# mk312lite_V4a.net
KiCad netlist of a schematic drawn in EAGLE
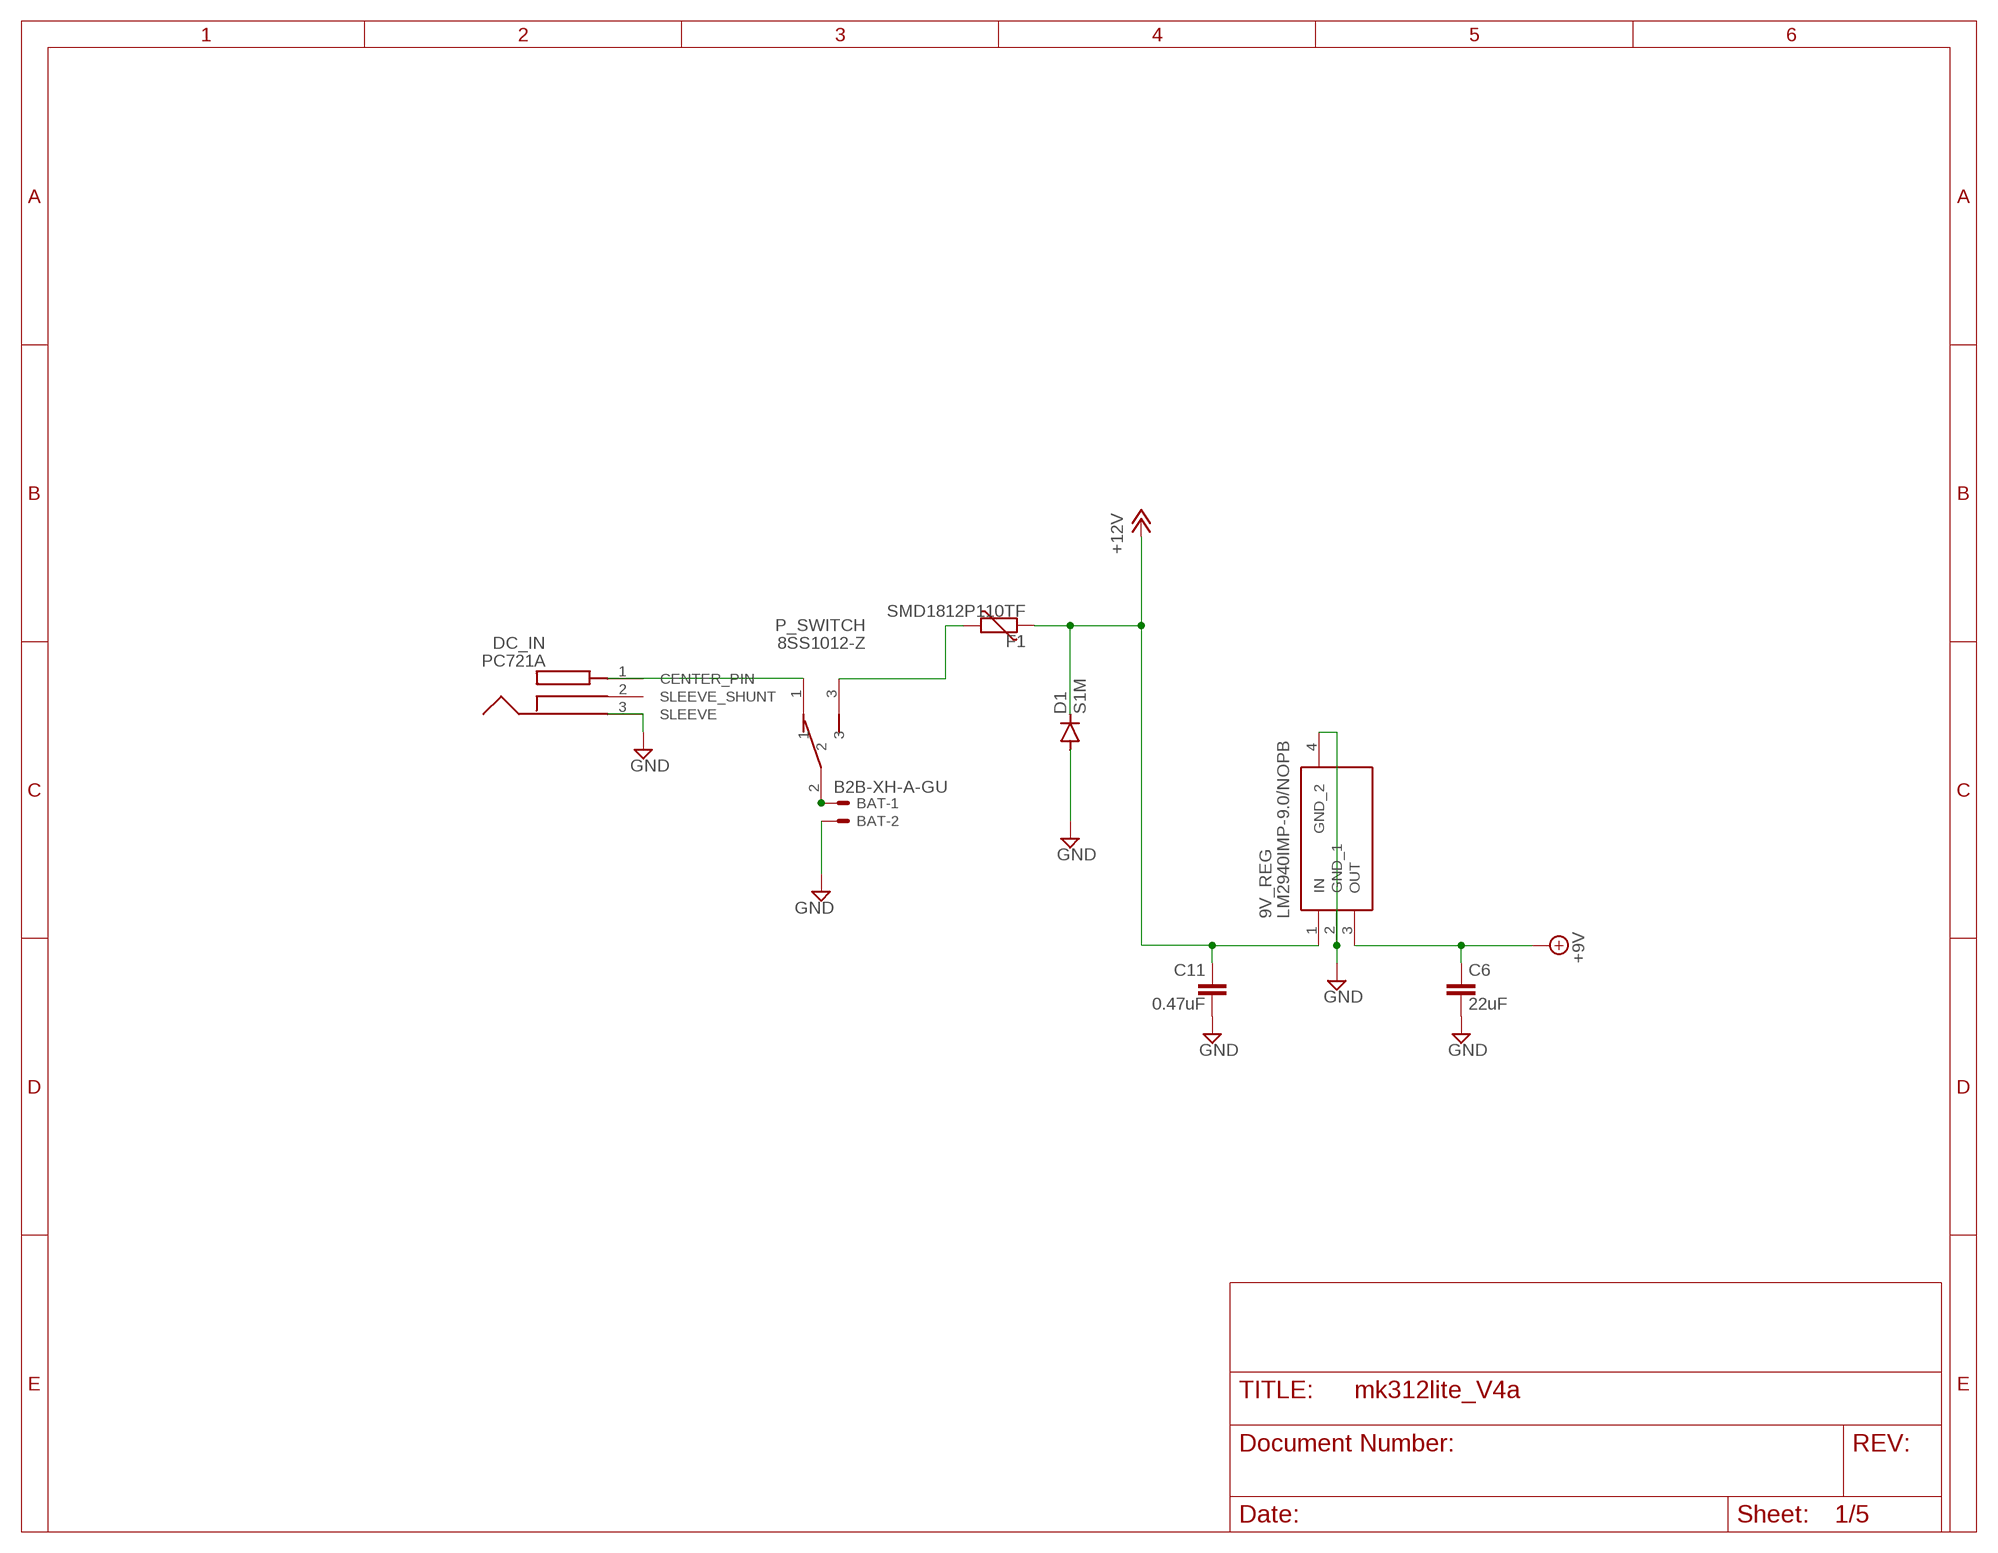
[diagram p0: schematic, sheet 1]
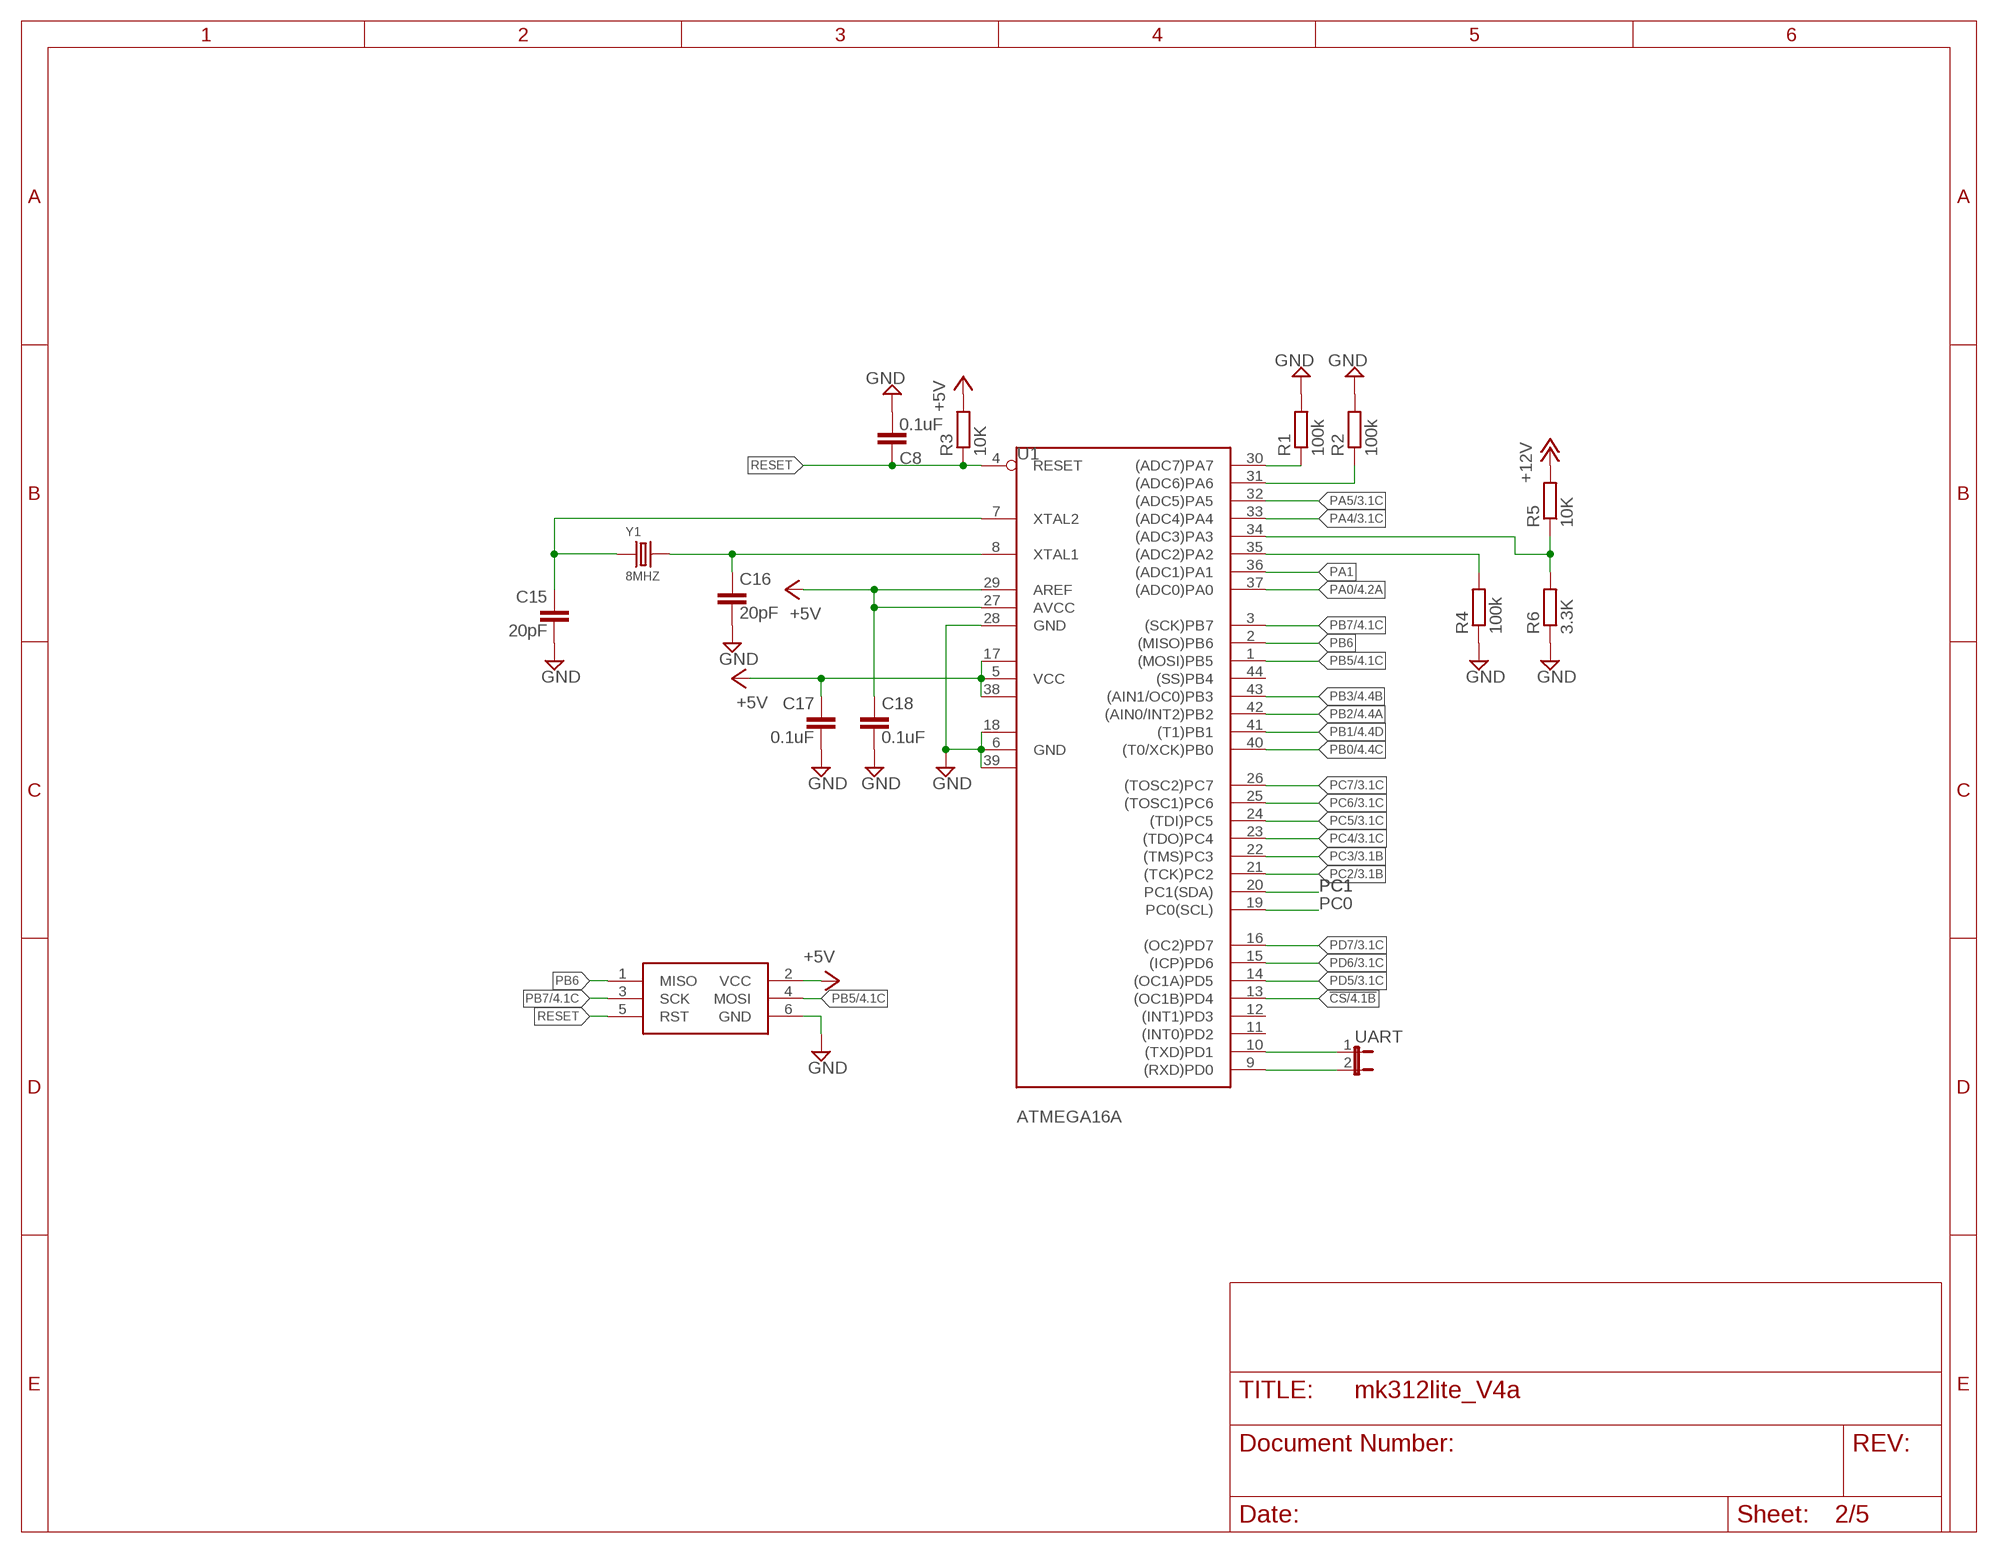
[diagram p1: schematic, sheet 2]
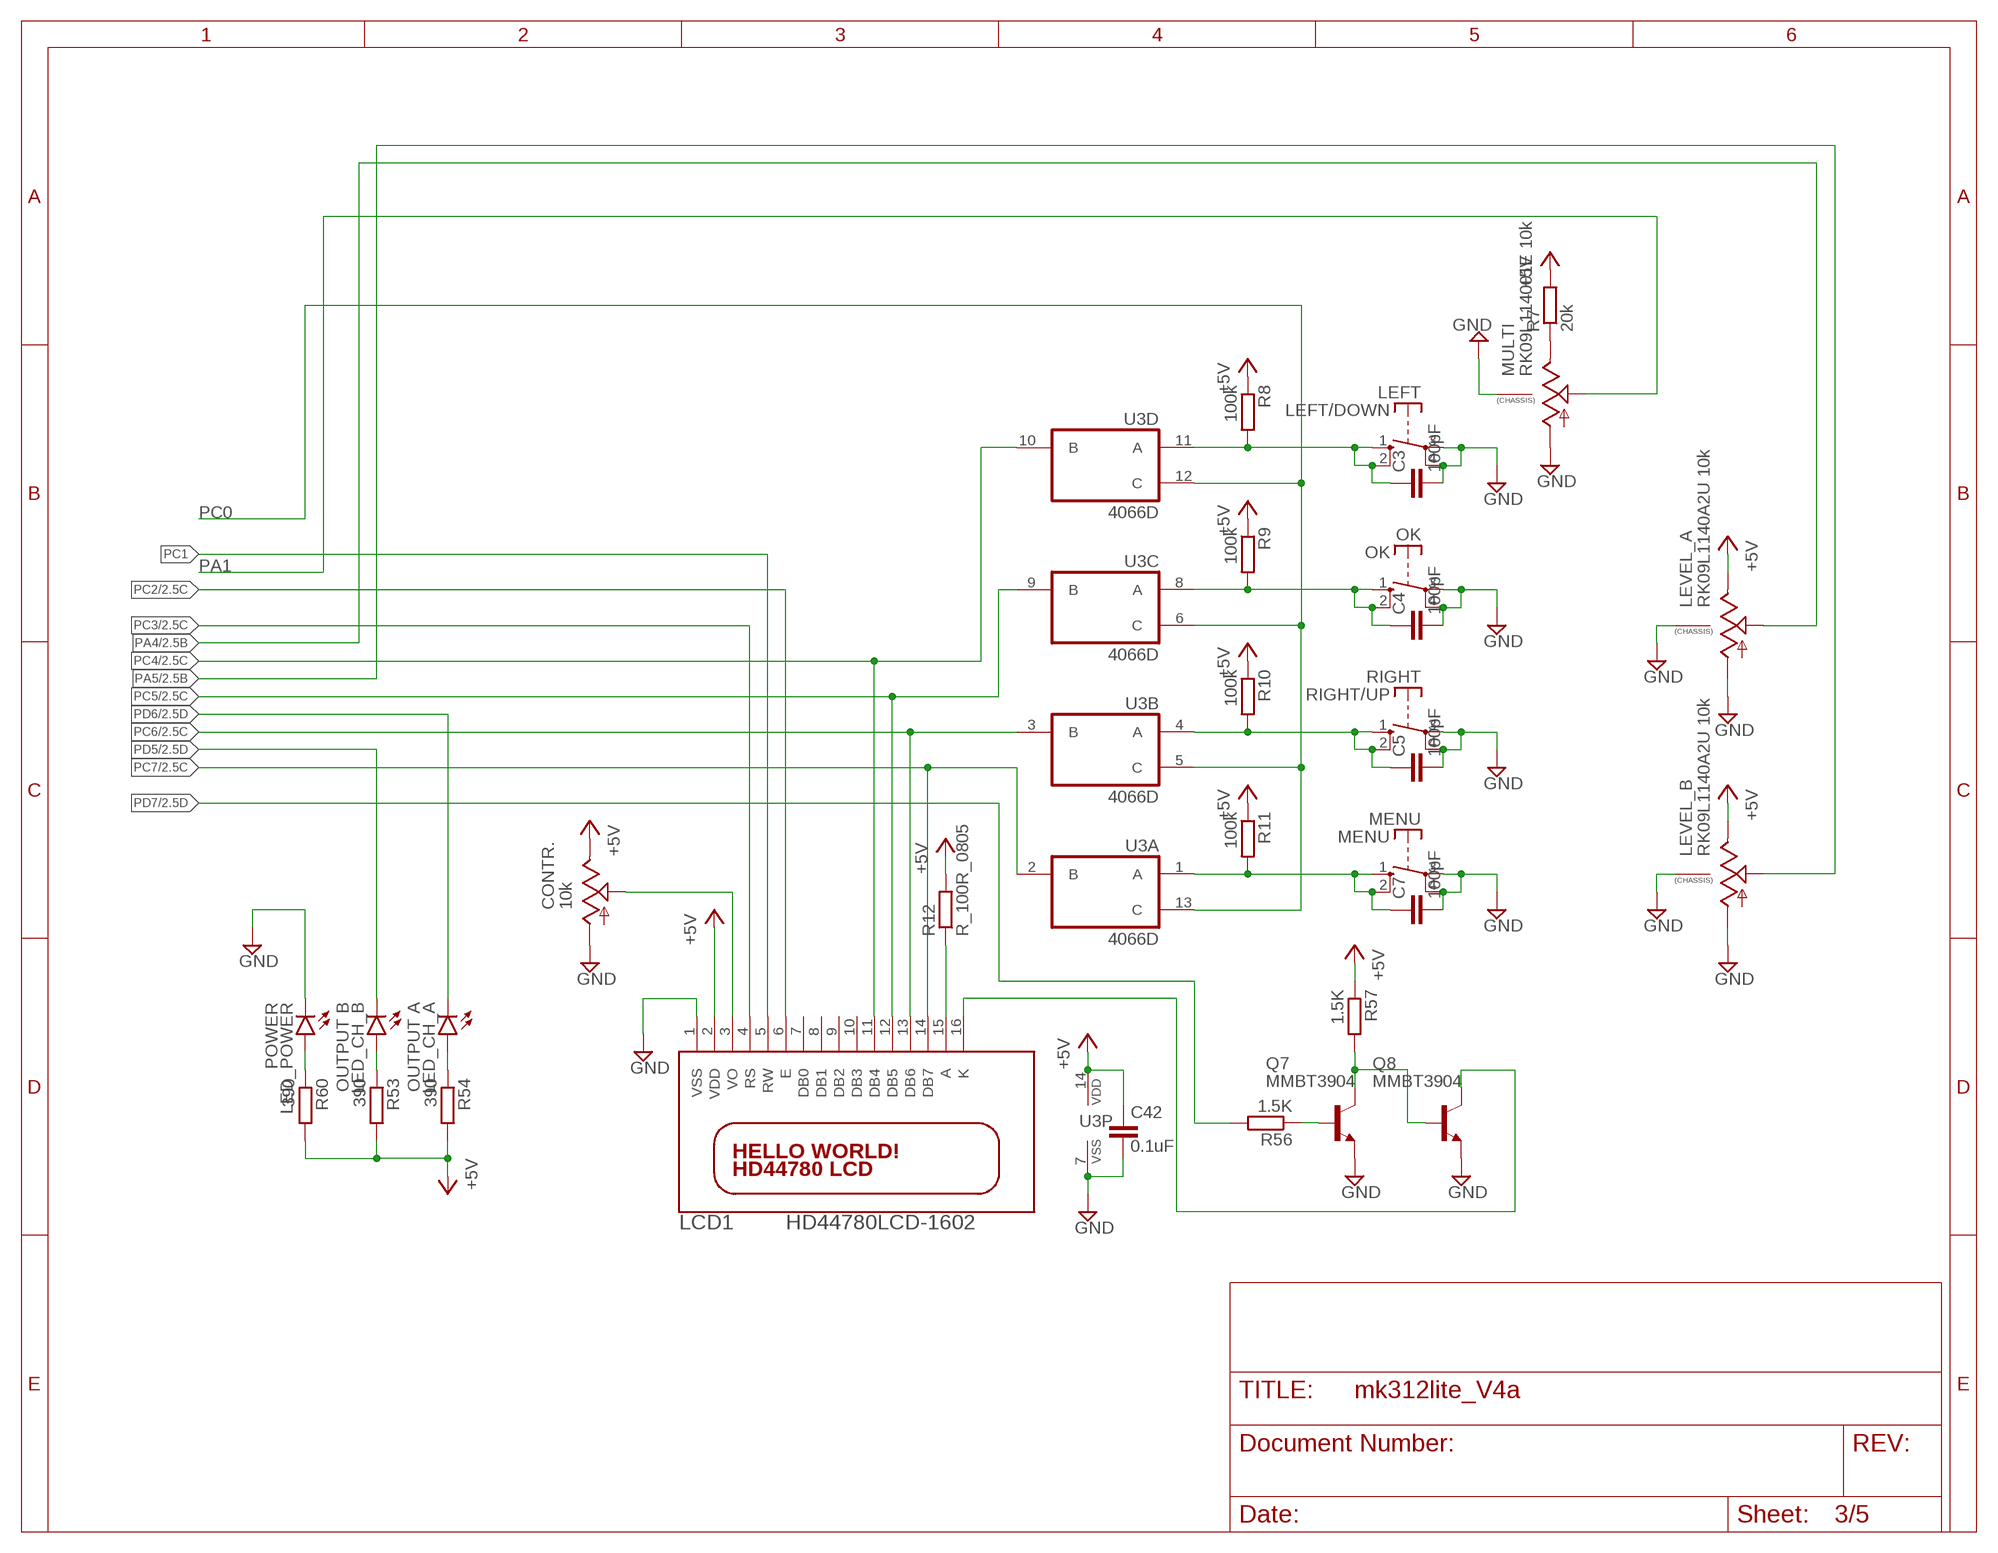
[diagram p2: schematic, sheet 3]
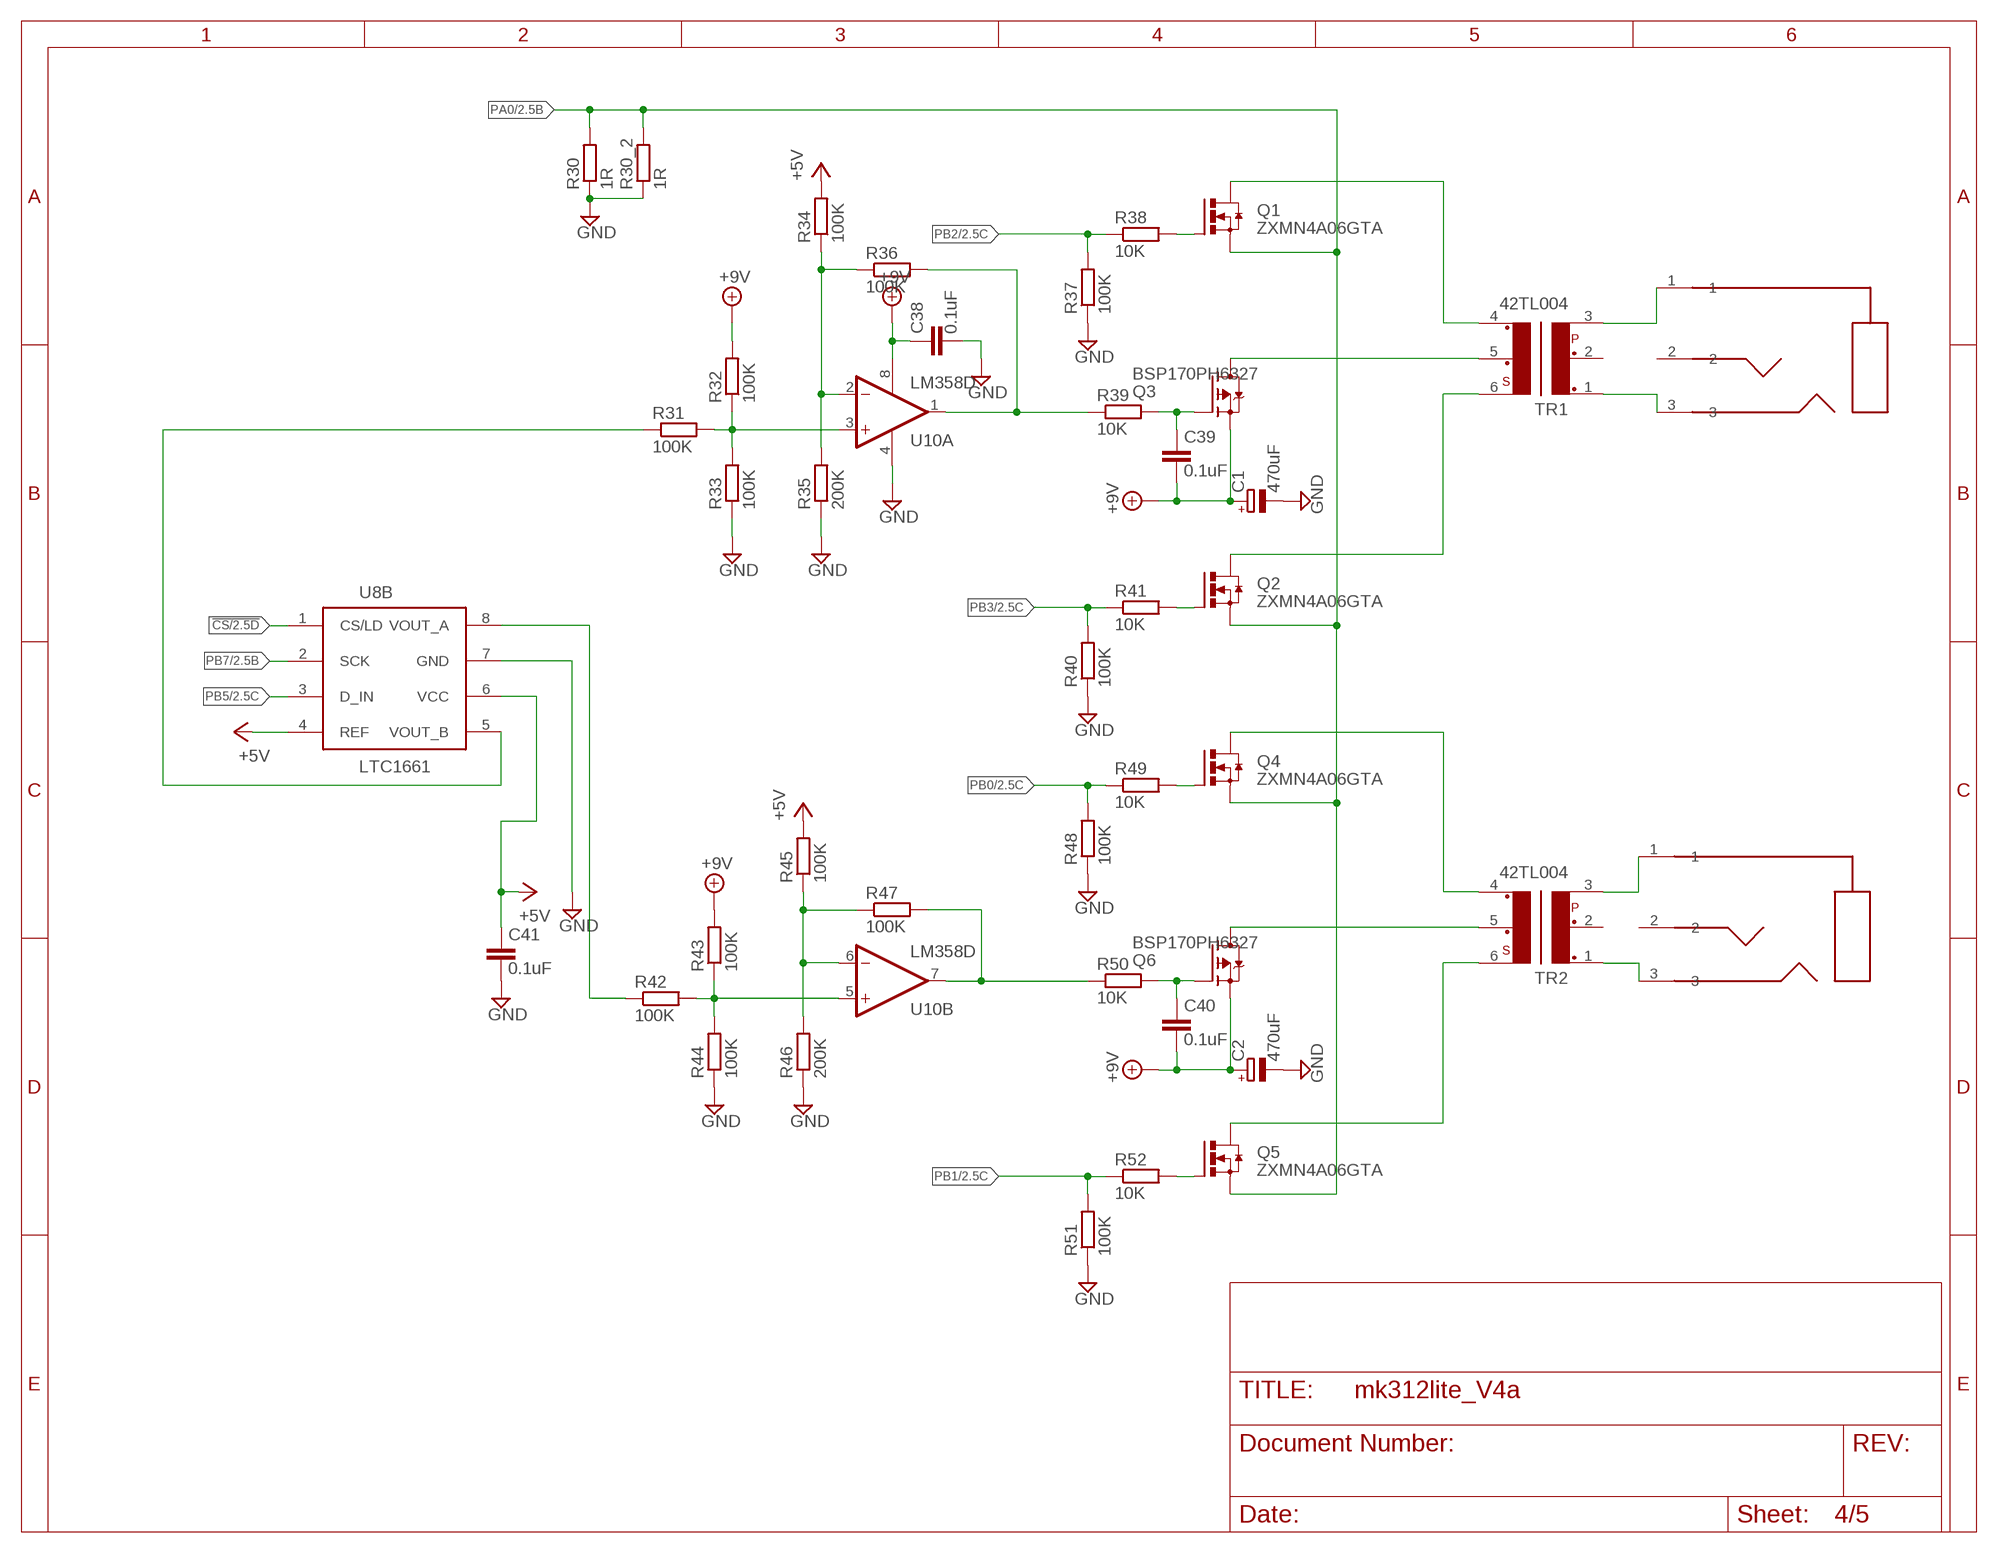
[diagram p3: schematic, sheet 4]
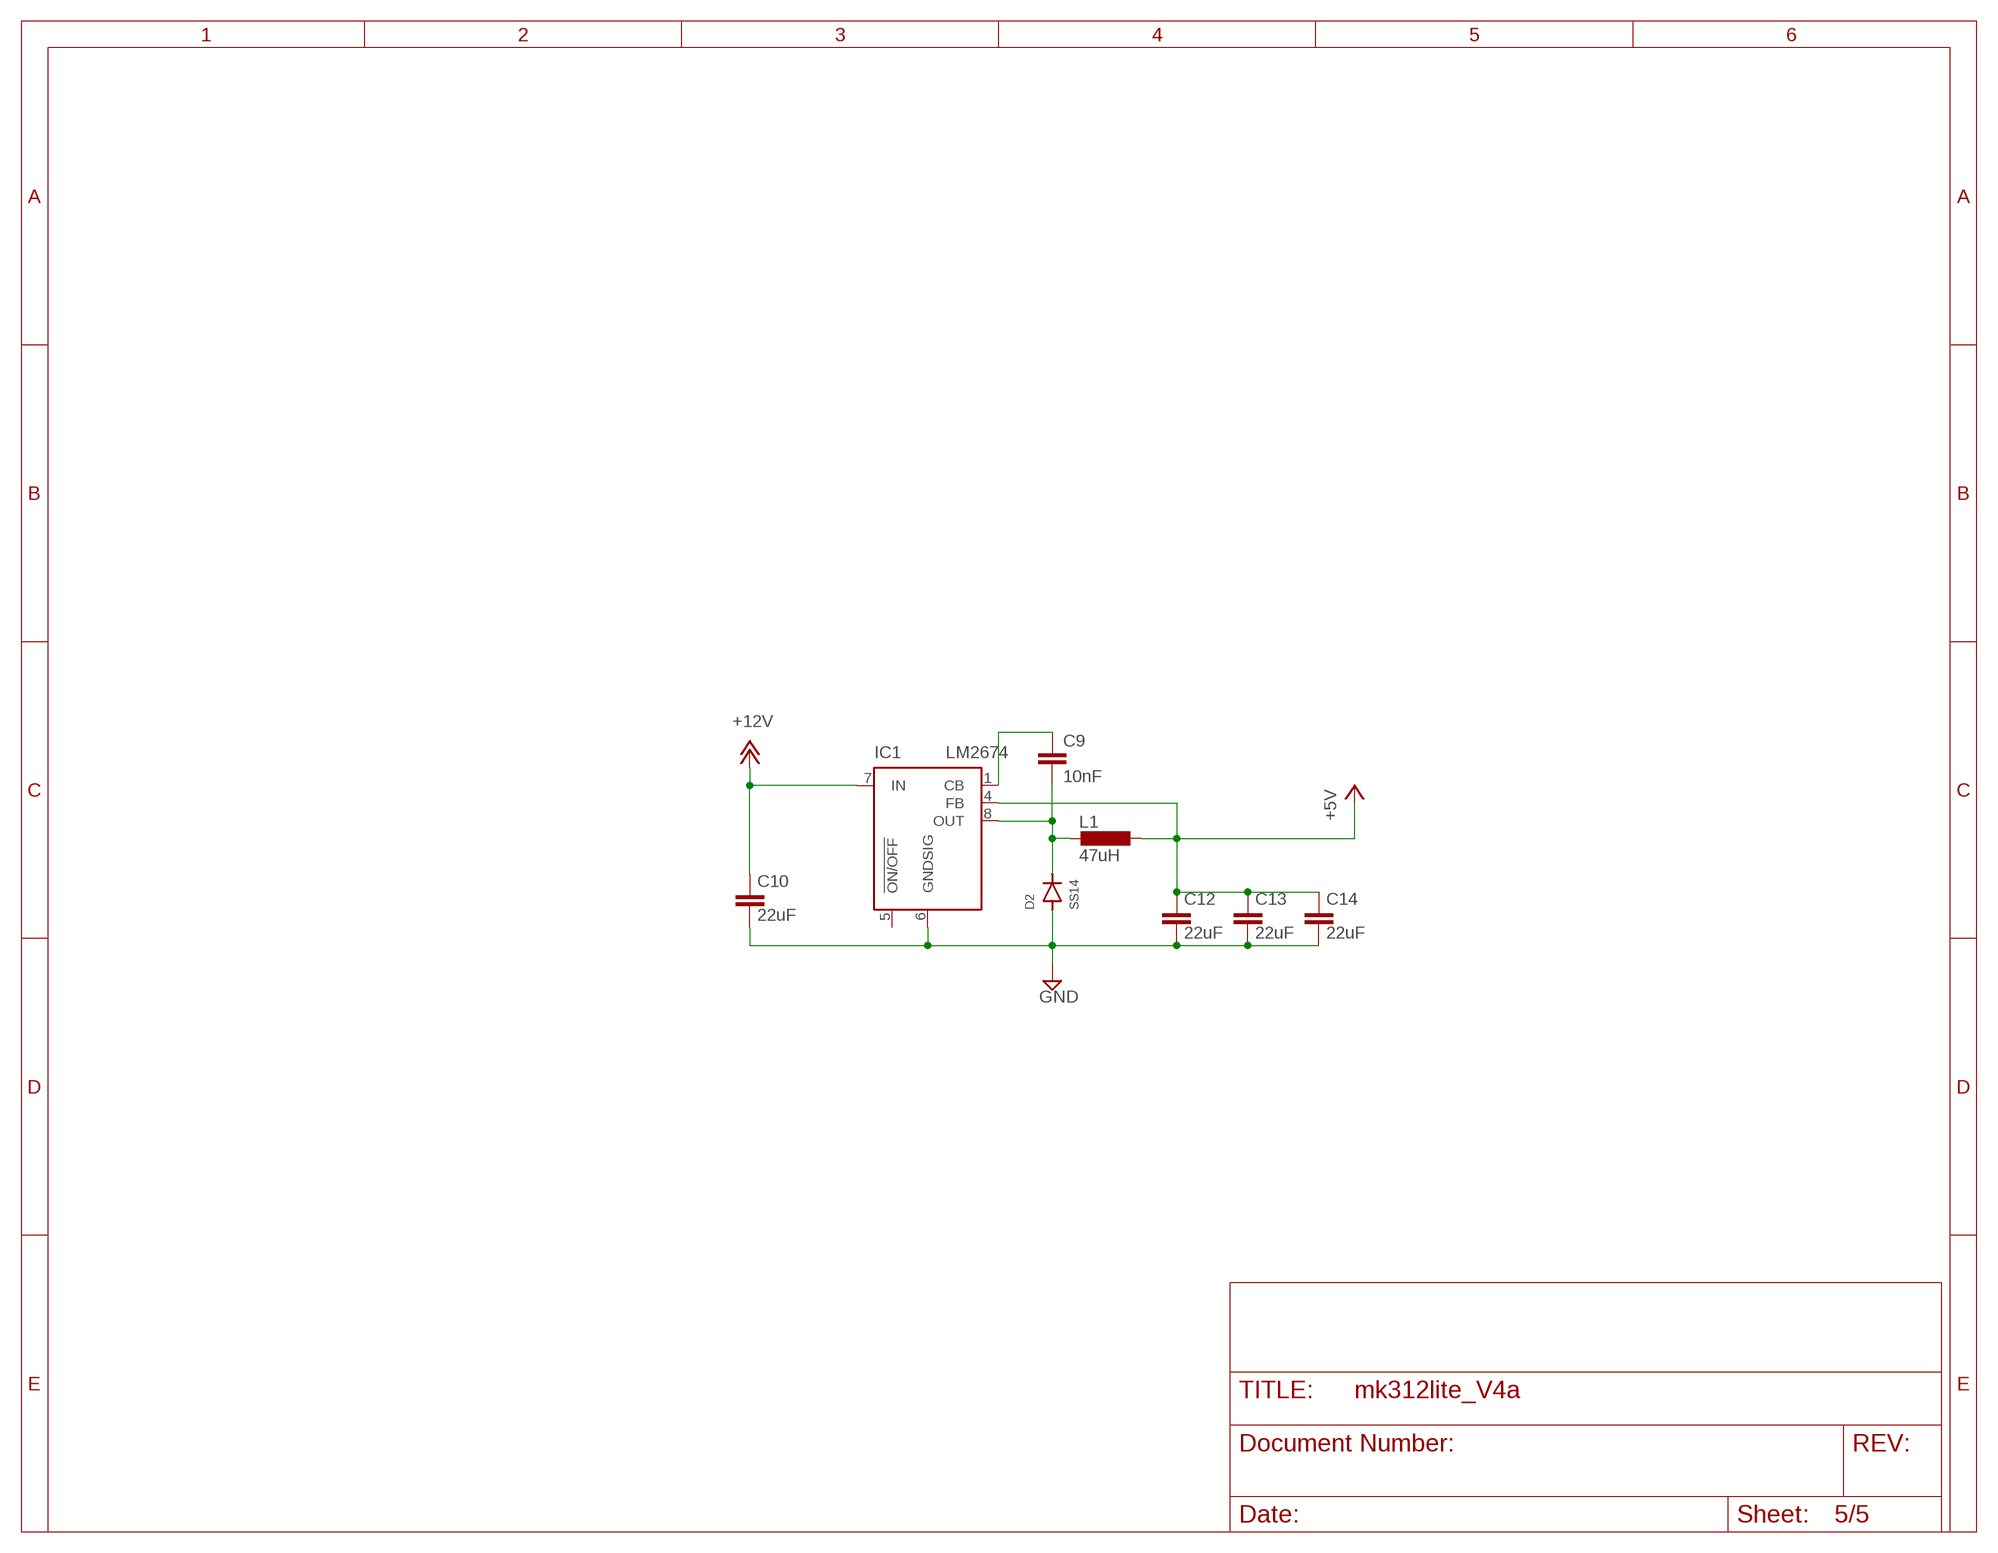
[diagram p4: schematic, sheet 5]

(export (version "E")
  (design (tool "Eeschema 10.0.6"))
  (components
    (comp (ref "9V_REG")
      (value "LM2940IMP-9.0/NOPB")
      (footprint "eagle-import:SOT230P700X180-4N")
      (fields (field (name "MOUSER_PART_NUMBER") "926-LM2940IMP90NOPB"))
      (libsource (lib "eagle-import") (part "LM2940IMP-9.0_NOPB"))
    )
    (comp (ref "BAT")
      (value "B2B-XH-A-GU")
      (footprint "eagle-import:JST-XH-02-PACKAGE-LONG-PAD")
      (libsource (lib "eagle-import") (part "JST-XH-02-PIN-LONG-PAD"))
    )
    (comp (ref "C6")
      (value "22uF")
      (footprint "eagle-import:C1206")
      (libsource (lib "eagle-import") (part "C-EUC1206"))
    )
    (comp (ref "C11")
      (value "0.47uF")
      (footprint "eagle-import:C0805")
      (libsource (lib "eagle-import") (part "C-EUC0805"))
    )
    (comp (ref "D1")
      (value "S1M")
      (footprint "eagle-import:SMA")
      (libsource (lib "eagle-import") (part "S1M"))
    )
    (comp (ref "DC_IN")
      (value "PC721A")
      (footprint "eagle-import:PC721A")
      (fields (field (name "MOUSER_PART_NUMBER") "502-PC721A"))
      (libsource (lib "eagle-import") (part "PC721A"))
    )
    (comp (ref "F1")
      (value "SMD1812P110TF")
      (footprint "eagle-import:CT_CN1812")
      (libsource (lib "eagle-import") (part "VARISTORCN1812"))
    )
    (comp (ref "P_SWITCH")
      (value "8SS1012-Z")
      (footprint "eagle-import:8SS1012Z")
      (libsource (lib "eagle-import") (part "8SS1012-Z"))
    )
    (comp (ref "C3")
      (value "100pF")
      (footprint "eagle-import:C0805")
      (libsource (lib "eagle-import") (part "C-EUC0805"))
    )
    (comp (ref "C4")
      (value "100pF")
      (footprint "eagle-import:C0805")
      (libsource (lib "eagle-import") (part "C-EUC0805"))
    )
    (comp (ref "C5")
      (value "100pF")
      (footprint "eagle-import:C0805")
      (libsource (lib "eagle-import") (part "C-EUC0805"))
    )
    (comp (ref "C7")
      (value "100pF")
      (footprint "eagle-import:C0805")
      (libsource (lib "eagle-import") (part "C-EUC0805"))
    )
    (comp (ref "C42")
      (value "0.1uF")
      (footprint "eagle-import:C0805")
      (libsource (lib "eagle-import") (part "C-EUC0805"))
    )
    (comp (ref "CONTR.")
      (value "10k")
      (footprint "eagle-import:B25P")
      (libsource (lib "eagle-import") (part "TRIM_US-B25P"))
    )
    (comp (ref "LCD1")
      (value "HD44780LCD-1602")
      (footprint "eagle-import:LCD1602")
      (libsource (lib "eagle-import") (part "HD44780LCD-1602"))
    )
    (comp (ref "LED_CH_A")
      (value "OUTPUT A")
      (footprint "eagle-import:LED3MM")
      (libsource (lib "eagle-import") (part "LED3MM"))
    )
    (comp (ref "LED_CH_B")
      (value "OUTPUT B")
      (footprint "eagle-import:LED3MM")
      (libsource (lib "eagle-import") (part "LED3MM"))
    )
    (comp (ref "LED_POWER")
      (value "POWER")
      (footprint "eagle-import:LED3MM")
      (libsource (lib "eagle-import") (part "LED3MM"))
    )
    (comp (ref "LEFT")
      (value "LEFT/DOWN")
      (footprint "eagle-import:DTE6K")
      (libsource (lib "eagle-import") (part "DTE6K"))
    )
    (comp (ref "LEVEL_A")
      (value "RK09L1140A2U 10k")
      (footprint "eagle-import:9MM_SNAP-IN_POT")
      (libsource (lib "eagle-import") (part "9MM_SNAP-IN_POT_CHASSIS"))
    )
    (comp (ref "LEVEL_B")
      (value "RK09L1140A2U 10k")
      (footprint "eagle-import:9MM_SNAP-IN_POT")
      (libsource (lib "eagle-import") (part "9MM_SNAP-IN_POT_CHASSIS"))
    )
    (comp (ref "MENU")
      (value "MENU")
      (footprint "eagle-import:DTE6K")
      (libsource (lib "eagle-import") (part "DTE6K"))
    )
    (comp (ref "MULTI")
      (value "RK09L114001E 10k")
      (footprint "eagle-import:9MM_SNAP-IN_POT")
      (libsource (lib "eagle-import") (part "9MM_SNAP-IN_POT_CHASSIS"))
    )
    (comp (ref "OK")
      (value "OK")
      (footprint "eagle-import:DTE6K")
      (libsource (lib "eagle-import") (part "DTE6K"))
    )
    (comp (ref "Q7")
      (value "MMBT3904")
      (footprint "eagle-import:SOT23-BEC")
      (libsource (lib "eagle-import") (part "-NPN-SOT23-BECMMBT3904LT1"))
    )
    (comp (ref "Q8")
      (value "MMBT3904")
      (footprint "eagle-import:SOT23-BEC")
      (libsource (lib "eagle-import") (part "-NPN-SOT23-BECMMBT3904LT1"))
    )
    (comp (ref "R7")
      (value "20k")
      (footprint "eagle-import:R0805")
      (libsource (lib "eagle-import") (part "R-EU_R0805"))
    )
    (comp (ref "R8")
      (value "100k")
      (footprint "eagle-import:R0805")
      (libsource (lib "eagle-import") (part "R-EU_R0805"))
    )
    (comp (ref "R9")
      (value "100k")
      (footprint "eagle-import:R0805")
      (libsource (lib "eagle-import") (part "R-EU_R0805"))
    )
    (comp (ref "R10")
      (value "100k")
      (footprint "eagle-import:R0805")
      (libsource (lib "eagle-import") (part "R-EU_R0805"))
    )
    (comp (ref "R11")
      (value "100k")
      (footprint "eagle-import:R0805")
      (libsource (lib "eagle-import") (part "R-EU_R0805"))
    )
    (comp (ref "R12")
      (value "R_100R_0805")
      (footprint "eagle-import:R0805")
      (fields (field (name "LCSC_PART") "C17408"))
      (libsource (lib "eagle-import") (part "R__0805100R"))
    )
    (comp (ref "R53")
      (value "390")
      (footprint "eagle-import:R0805")
      (libsource (lib "eagle-import") (part "R-EU_R0805"))
    )
    (comp (ref "R54")
      (value "390")
      (footprint "eagle-import:R0805")
      (libsource (lib "eagle-import") (part "R-EU_R0805"))
    )
    (comp (ref "R56")
      (value "1.5K")
      (footprint "eagle-import:R0805")
      (libsource (lib "eagle-import") (part "R-EU_R0805"))
    )
    (comp (ref "R57")
      (value "1.5K")
      (footprint "eagle-import:R0805")
      (libsource (lib "eagle-import") (part "R-EU_R0805"))
    )
    (comp (ref "R60")
      (value "390")
      (footprint "eagle-import:R0805")
      (libsource (lib "eagle-import") (part "R-EU_R0805"))
    )
    (comp (ref "RIGHT")
      (value "RIGHT/UP")
      (footprint "eagle-import:DTE6K")
      (libsource (lib "eagle-import") (part "DTE6K"))
    )
    (comp (ref "U3")
      (value "4066D")
      (footprint "eagle-import:SO14")
      (libsource (lib "eagle-import") (part "4066D"))
    )
    (comp (ref "C1")
      (value "470uF")
      (footprint "eagle-import:150CLZ-1010")
      (libsource (lib "eagle-import") (part "CPOL-EU150CLZ-1010"))
    )
    (comp (ref "C2")
      (value "470uF")
      (footprint "eagle-import:150CLZ-1010")
      (libsource (lib "eagle-import") (part "CPOL-EU150CLZ-1010"))
    )
    (comp (ref "C38")
      (value "0.1uF")
      (footprint "eagle-import:C0805")
      (libsource (lib "eagle-import") (part "C-EUC0805"))
    )
    (comp (ref "C39")
      (value "0.1uF")
      (footprint "eagle-import:C0805")
      (libsource (lib "eagle-import") (part "C-EUC0805"))
    )
    (comp (ref "C40")
      (value "0.1uF")
      (footprint "eagle-import:C0805")
      (libsource (lib "eagle-import") (part "C-EUC0805"))
    )
    (comp (ref "C41")
      (value "0.1uF")
      (footprint "eagle-import:C0805")
      (libsource (lib "eagle-import") (part "C-EUC0805"))
    )
    (comp (ref "CHAN_A")
      (value "PJ-301C")
      (footprint "eagle-import:PJ-301C")
      (libsource (lib "eagle-import") (part "PC-301C"))
    )
    (comp (ref "CHAN_B")
      (value "PJ-301C")
      (footprint "eagle-import:PJ-301C")
      (libsource (lib "eagle-import") (part "PC-301C"))
    )
    (comp (ref "Q1")
      (value "ZXMN4A06GTA")
      (footprint "eagle-import:SOT223")
      (libsource (lib "eagle-import") (part "N-HEXFET-2D_?-SOT232IRLL2705"))
    )
    (comp (ref "Q2")
      (value "ZXMN4A06GTA")
      (footprint "eagle-import:SOT223")
      (libsource (lib "eagle-import") (part "N-HEXFET-2D_?-SOT232IRLL2705"))
    )
    (comp (ref "Q3")
      (value "BSP170PH6327")
      (footprint "eagle-import:SOT230P700X180-4N")
      (libsource (lib "eagle-import") (part "IRFL9014TRPBF"))
    )
    (comp (ref "Q4")
      (value "ZXMN4A06GTA")
      (footprint "eagle-import:SOT223")
      (libsource (lib "eagle-import") (part "N-HEXFET-2D_?-SOT232IRLL2705"))
    )
    (comp (ref "Q5")
      (value "ZXMN4A06GTA")
      (footprint "eagle-import:SOT223")
      (libsource (lib "eagle-import") (part "N-HEXFET-2D_?-SOT232IRLL2705"))
    )
    (comp (ref "Q6")
      (value "BSP170PH6327")
      (footprint "eagle-import:SOT230P700X180-4N")
      (libsource (lib "eagle-import") (part "IRFL9014TRPBF"))
    )
    (comp (ref "R30")
      (value "1R")
      (footprint "eagle-import:R1206")
      (libsource (lib "eagle-import") (part "R-EU_R1206"))
    )
    (comp (ref "R30_2")
      (value "1R")
      (footprint "eagle-import:R1206")
      (libsource (lib "eagle-import") (part "R-EU_R1206"))
    )
    (comp (ref "R31")
      (value "100K")
      (footprint "eagle-import:R0805")
      (libsource (lib "eagle-import") (part "R-EU_R0805"))
    )
    (comp (ref "R32")
      (value "100K")
      (footprint "eagle-import:R0805")
      (libsource (lib "eagle-import") (part "R-EU_R0805"))
    )
    (comp (ref "R33")
      (value "100K")
      (footprint "eagle-import:R0805")
      (libsource (lib "eagle-import") (part "R-EU_R0805"))
    )
    (comp (ref "R34")
      (value "100K")
      (footprint "eagle-import:R0805")
      (libsource (lib "eagle-import") (part "R-EU_R0805"))
    )
    (comp (ref "R35")
      (value "200K")
      (footprint "eagle-import:R0805")
      (libsource (lib "eagle-import") (part "R-EU_R0805"))
    )
    (comp (ref "R36")
      (value "100K")
      (footprint "eagle-import:R0805")
      (libsource (lib "eagle-import") (part "R-EU_R0805"))
    )
    (comp (ref "R37")
      (value "100K")
      (footprint "eagle-import:R0805")
      (libsource (lib "eagle-import") (part "R-EU_R0805"))
    )
    (comp (ref "R38")
      (value "10K")
      (footprint "eagle-import:R0805")
      (libsource (lib "eagle-import") (part "R-EU_R0805"))
    )
    (comp (ref "R39")
      (value "10K")
      (footprint "eagle-import:R0805")
      (libsource (lib "eagle-import") (part "R-EU_R0805"))
    )
    (comp (ref "R40")
      (value "100K")
      (footprint "eagle-import:R0805")
      (libsource (lib "eagle-import") (part "R-EU_R0805"))
    )
    (comp (ref "R41")
      (value "10K")
      (footprint "eagle-import:R0805")
      (libsource (lib "eagle-import") (part "R-EU_R0805"))
    )
    (comp (ref "R42")
      (value "100K")
      (footprint "eagle-import:R0805")
      (libsource (lib "eagle-import") (part "R-EU_R0805"))
    )
    (comp (ref "R43")
      (value "100K")
      (footprint "eagle-import:R0805")
      (libsource (lib "eagle-import") (part "R-EU_R0805"))
    )
    (comp (ref "R44")
      (value "100K")
      (footprint "eagle-import:R0805")
      (libsource (lib "eagle-import") (part "R-EU_R0805"))
    )
    (comp (ref "R45")
      (value "100K")
      (footprint "eagle-import:R0805")
      (libsource (lib "eagle-import") (part "R-EU_R0805"))
    )
    (comp (ref "R46")
      (value "200K")
      (footprint "eagle-import:R0805")
      (libsource (lib "eagle-import") (part "R-EU_R0805"))
    )
    (comp (ref "R47")
      (value "100K")
      (footprint "eagle-import:R0805")
      (libsource (lib "eagle-import") (part "R-EU_R0805"))
    )
    (comp (ref "R48")
      (value "100K")
      (footprint "eagle-import:R0805")
      (libsource (lib "eagle-import") (part "R-EU_R0805"))
    )
    (comp (ref "R49")
      (value "10K")
      (footprint "eagle-import:R0805")
      (libsource (lib "eagle-import") (part "R-EU_R0805"))
    )
    (comp (ref "R50")
      (value "10K")
      (footprint "eagle-import:R0805")
      (libsource (lib "eagle-import") (part "R-EU_R0805"))
    )
    (comp (ref "R51")
      (value "100K")
      (footprint "eagle-import:R0805")
      (libsource (lib "eagle-import") (part "R-EU_R0805"))
    )
    (comp (ref "R52")
      (value "10K")
      (footprint "eagle-import:R0805")
      (libsource (lib "eagle-import") (part "R-EU_R0805"))
    )
    (comp (ref "TR1")
      (value "42TL004")
      (footprint "eagle-import:42TL")
      (libsource (lib "eagle-import") (part "42T?L023"))
    )
    (comp (ref "TR2")
      (value "42TL004")
      (footprint "eagle-import:42TL")
      (libsource (lib "eagle-import") (part "42T?L023"))
    )
    (comp (ref "U8B")
      (value "LTC1661")
      (footprint "eagle-import:MSOP8")
      (libsource (lib "eagle-import") (part "LTC1661IMS8"))
    )
    (comp (ref "U10")
      (value "LM358D")
      (footprint "eagle-import:SO08")
      (libsource (lib "eagle-import") (part "LM358D"))
    )
    (comp (ref "C8")
      (value "0.1uF")
      (footprint "eagle-import:C0805")
      (libsource (lib "eagle-import") (part "C-EUC0805"))
    )
    (comp (ref "C15")
      (value "20pF")
      (footprint "eagle-import:C0603")
      (libsource (lib "eagle-import") (part "C-EUC0603"))
    )
    (comp (ref "C16")
      (value "20pF")
      (footprint "eagle-import:C0603")
      (libsource (lib "eagle-import") (part "C-EUC0603"))
    )
    (comp (ref "C17")
      (value "0.1uF")
      (footprint "eagle-import:C0805")
      (libsource (lib "eagle-import") (part "C-EUC0805"))
    )
    (comp (ref "C18")
      (value "0.1uF")
      (footprint "eagle-import:C0805")
      (libsource (lib "eagle-import") (part "C-EUC0805"))
    )
    (comp (ref "ISP1")
      (value "AVRISP-6")
      (footprint "eagle-import:AVRISP")
      (libsource (lib "eagle-import") (part "AVRISP-6"))
    )
    (comp (ref "R1")
      (value "100k")
      (footprint "eagle-import:R0805")
      (libsource (lib "eagle-import") (part "R-EU_R0805"))
    )
    (comp (ref "R2")
      (value "100k")
      (footprint "eagle-import:R0805")
      (libsource (lib "eagle-import") (part "R-EU_R0805"))
    )
    (comp (ref "R3")
      (value "10K")
      (footprint "eagle-import:R0805")
      (libsource (lib "eagle-import") (part "R-EU_R0805"))
    )
    (comp (ref "R4")
      (value "100k")
      (footprint "eagle-import:R0805")
      (libsource (lib "eagle-import") (part "R-EU_R0805"))
    )
    (comp (ref "R5")
      (value "10K")
      (footprint "eagle-import:R0805")
      (libsource (lib "eagle-import") (part "R-EU_R0805"))
    )
    (comp (ref "R6")
      (value "3.3K")
      (footprint "eagle-import:R0805")
      (libsource (lib "eagle-import") (part "R-EU_R0805"))
    )
    (comp (ref "U1")
      (value "ATMEGA16A")
      (footprint "eagle-import:TQFP44")
      (fields (field (name "MPN") "ATMEGA16-16AU"))
      (libsource (lib "eagle-import") (part "MEGA16-A"))
    )
    (comp (ref "UART")
      (value "JP1E")
      (footprint "eagle-import:JP1")
      (libsource (lib "eagle-import") (part "JP1E"))
    )
    (comp (ref "Y1")
      (value "8MHZ")
      (footprint "eagle-import:X2-SMD-5.0X3.2X1.3MM")
      (fields (field (name "MPN") "5032/2P"))
      (libsource (lib "eagle-import") (part "SMD-CRYSTAL-8MHZ-20PF-20PPM(2P-5.0X3.2MM)"))
    )
    (comp (ref "C9")
      (value "10nF")
      (footprint "eagle-import:C0805")
      (libsource (lib "eagle-import") (part "C-EUC0805"))
    )
    (comp (ref "C10")
      (value "22uF")
      (footprint "eagle-import:C1206")
      (libsource (lib "eagle-import") (part "C-EUC1206"))
    )
    (comp (ref "C12")
      (value "22uF")
      (footprint "eagle-import:C1206")
      (libsource (lib "eagle-import") (part "C-EUC1206"))
    )
    (comp (ref "C13")
      (value "22uF")
      (footprint "eagle-import:C1206")
      (libsource (lib "eagle-import") (part "C-EUC1206"))
    )
    (comp (ref "C14")
      (value "22uF")
      (footprint "eagle-import:C1206")
      (libsource (lib "eagle-import") (part "C-EUC1206"))
    )
    (comp (ref "D2")
      (value "SS14")
      (footprint "eagle-import:SMA")
      (libsource (lib "eagle-import") (part "S1M"))
    )
    (comp (ref "IC1")
      (value "LM2674")
      (footprint "eagle-import:SO08")
      (libsource (lib "eagle-import") (part "LM2674"))
    )
    (comp (ref "L1")
      (value "47uH")
      (footprint "eagle-import:SMNR4030-151MT")
      (libsource (lib "eagle-import") (part "SMNR4030-151MT"))
    )
  )
  (nets
    (net (code "1") (name "+5V") (class "Default")
      (node (ref "C12") (pin "1") (pinfunction "1_1") (pintype "passive"))
      (node (ref "C13") (pin "1") (pinfunction "1_1") (pintype "passive"))
      (node (ref "C14") (pin "1") (pinfunction "1_1") (pintype "passive"))
      (node (ref "C17") (pin "1") (pinfunction "1_1") (pintype "passive"))
      (node (ref "C18") (pin "1") (pinfunction "1_1") (pintype "passive"))
      (node (ref "C41") (pin "1") (pinfunction "1_1") (pintype "passive"))
      (node (ref "C42") (pin "1") (pinfunction "1_1") (pintype "passive"))
      (node (ref "CONTR.") (pin "E") (pinfunction "E_E") (pintype "passive"))
      (node (ref "IC1") (pin "4") (pinfunction "FB_4") (pintype "input"))
      (node (ref "ISP1") (pin "2") (pinfunction "VCC_2") (pintype "power_in"))
      (node (ref "L1") (pin "2") (pinfunction "2_2") (pintype "passive"))
      (node (ref "LCD1") (pin "2") (pinfunction "VDD_2") (pintype "power_in"))
      (node (ref "LEVEL_A") (pin "3") (pinfunction "E_3") (pintype "passive"))
      (node (ref "LEVEL_B") (pin "3") (pinfunction "E_3") (pintype "passive"))
      (node (ref "R10") (pin "1") (pinfunction "1_1") (pintype "passive"))
      (node (ref "R11") (pin "1") (pinfunction "1_1") (pintype "passive"))
      (node (ref "R12") (pin "2") (pinfunction "2_2") (pintype "passive"))
      (node (ref "R3") (pin "2") (pinfunction "2_2") (pintype "passive"))
      (node (ref "R34") (pin "2") (pinfunction "2_2") (pintype "passive"))
      (node (ref "R45") (pin "2") (pinfunction "2_2") (pintype "passive"))
      (node (ref "R53") (pin "2") (pinfunction "2_2") (pintype "passive"))
      (node (ref "R54") (pin "2") (pinfunction "2_2") (pintype "passive"))
      (node (ref "R57") (pin "1") (pinfunction "1_1") (pintype "passive"))
      (node (ref "R60") (pin "2") (pinfunction "2_2") (pintype "passive"))
      (node (ref "R7") (pin "2") (pinfunction "2_2") (pintype "passive"))
      (node (ref "R8") (pin "1") (pinfunction "1_1") (pintype "passive"))
      (node (ref "R9") (pin "1") (pinfunction "1_1") (pintype "passive"))
      (node (ref "U1") (pin "17") (pinfunction "VCC1_17") (pintype "power_in"))
      (node (ref "U1") (pin "27") (pinfunction "AVCC_27") (pintype "power_in"))
      (node (ref "U1") (pin "29") (pinfunction "AREF_29") (pintype "passive"))
      (node (ref "U1") (pin "38") (pinfunction "VCC2_38") (pintype "power_in"))
      (node (ref "U1") (pin "5") (pinfunction "VCC_5") (pintype "power_in"))
      (node (ref "U3") (pin "14") (pinfunction "VDD_14") (pintype "power_in"))
      (node (ref "U8B") (pin "4") (pinfunction "REF_4") (pintype "input"))
      (node (ref "U8B") (pin "6") (pinfunction "VCC_6") (pintype "power_in"))
    )
    (net (code "2") (name "+9V") (class "Default")
      (node (ref "9V_REG") (pin "3") (pinfunction "OUT_3") (pintype "bidirectional"))
      (node (ref "C1") (pin "+") (pinfunction "+_+") (pintype "passive"))
      (node (ref "C2") (pin "+") (pinfunction "+_+") (pintype "passive"))
      (node (ref "C38") (pin "1") (pinfunction "1_1") (pintype "passive"))
      (node (ref "C39") (pin "2") (pinfunction "2_2") (pintype "passive"))
      (node (ref "C40") (pin "2") (pinfunction "2_2") (pintype "passive"))
      (node (ref "C6") (pin "1") (pinfunction "1_1") (pintype "passive"))
      (node (ref "Q3") (pin "3") (pinfunction "S_3") (pintype "passive"))
      (node (ref "Q6") (pin "3") (pinfunction "S_3") (pintype "passive"))
      (node (ref "R32") (pin "2") (pinfunction "2_2") (pintype "passive"))
      (node (ref "R43") (pin "2") (pinfunction "2_2") (pintype "passive"))
      (node (ref "U10") (pin "8") (pinfunction "V+_8") (pintype "power_in"))
    )
    (net (code "3") (name "+12V") (class "Default")
      (node (ref "9V_REG") (pin "1") (pinfunction "IN_1") (pintype "bidirectional"))
      (node (ref "C10") (pin "1") (pinfunction "1_1") (pintype "passive"))
      (node (ref "C11") (pin "1") (pinfunction "1_1") (pintype "passive"))
      (node (ref "D1") (pin "C") (pinfunction "C_C") (pintype "passive"))
      (node (ref "F1") (pin "2") (pinfunction "2_2") (pintype "passive"))
      (node (ref "IC1") (pin "7") (pinfunction "IN_7") (pintype "input"))
      (node (ref "R5") (pin "2") (pinfunction "2_2") (pintype "passive"))
    )
    (net (code "4") (name "GND") (class "Default")
      (node (ref "9V_REG") (pin "2") (pinfunction "GND_1_2") (pintype "bidirectional"))
      (node (ref "9V_REG") (pin "4") (pinfunction "GND_2_4") (pintype "bidirectional"))
      (node (ref "BAT") (pin "2") (pinfunction "S_2") (pintype "passive"))
      (node (ref "C1") (pin "-") (pinfunction "-_-") (pintype "passive"))
      (node (ref "C10") (pin "2") (pinfunction "2_2") (pintype "passive"))
      (node (ref "C11") (pin "2") (pinfunction "2_2") (pintype "passive"))
      (node (ref "C12") (pin "2") (pinfunction "2_2") (pintype "passive"))
      (node (ref "C13") (pin "2") (pinfunction "2_2") (pintype "passive"))
      (node (ref "C14") (pin "2") (pinfunction "2_2") (pintype "passive"))
      (node (ref "C15") (pin "2") (pinfunction "2_2") (pintype "passive"))
      (node (ref "C16") (pin "2") (pinfunction "2_2") (pintype "passive"))
      (node (ref "C17") (pin "2") (pinfunction "2_2") (pintype "passive"))
      (node (ref "C18") (pin "2") (pinfunction "2_2") (pintype "passive"))
      (node (ref "C2") (pin "-") (pinfunction "-_-") (pintype "passive"))
      (node (ref "C3") (pin "2") (pinfunction "2_2") (pintype "passive"))
      (node (ref "C38") (pin "2") (pinfunction "2_2") (pintype "passive"))
      (node (ref "C4") (pin "2") (pinfunction "2_2") (pintype "passive"))
      (node (ref "C41") (pin "2") (pinfunction "2_2") (pintype "passive"))
      (node (ref "C42") (pin "2") (pinfunction "2_2") (pintype "passive"))
      (node (ref "C5") (pin "2") (pinfunction "2_2") (pintype "passive"))
      (node (ref "C6") (pin "2") (pinfunction "2_2") (pintype "passive"))
      (node (ref "C7") (pin "2") (pinfunction "2_2") (pintype "passive"))
      (node (ref "C8") (pin "2") (pinfunction "2_2") (pintype "passive"))
      (node (ref "CONTR.") (pin "A") (pinfunction "A_A") (pintype "passive"))
      (node (ref "D1") (pin "A") (pinfunction "A_A") (pintype "passive"))
      (node (ref "D2") (pin "A") (pinfunction "A_A") (pintype "passive"))
      (node (ref "DC_IN") (pin "3") (pinfunction "SLEEVE_3") (pintype "bidirectional"))
      (node (ref "IC1") (pin "6") (pinfunction "GNDSIG_6") (pintype "input"))
      (node (ref "ISP1") (pin "6") (pinfunction "GND_6") (pintype "power_in"))
      (node (ref "LCD1") (pin "1") (pinfunction "VSS_1") (pintype "power_in"))
      (node (ref "LED_POWER") (pin "K") (pinfunction "C_K") (pintype "passive"))
      (node (ref "LEFT") (pin "3") (pinfunction "P_3") (pintype "passive"))
      (node (ref "LEFT") (pin "4") (pinfunction "P_4") (pintype "passive"))
      (node (ref "LEVEL_A") (pin "1") (pinfunction "A_1") (pintype "passive"))
      (node (ref "LEVEL_A") (pin "CHASSIS2") (pinfunction "P$1_CHASSIS2") (pintype "passive"))
      (node (ref "LEVEL_B") (pin "1") (pinfunction "A_1") (pintype "passive"))
      (node (ref "LEVEL_B") (pin "CHASSIS2") (pinfunction "P$1_CHASSIS2") (pintype "passive"))
      (node (ref "MENU") (pin "3") (pinfunction "P_3") (pintype "passive"))
      (node (ref "MENU") (pin "4") (pinfunction "P_4") (pintype "passive"))
      (node (ref "MULTI") (pin "1") (pinfunction "A_1") (pintype "passive"))
      (node (ref "MULTI") (pin "CHASSIS2") (pinfunction "P$1_CHASSIS2") (pintype "passive"))
      (node (ref "OK") (pin "3") (pinfunction "P_3") (pintype "passive"))
      (node (ref "OK") (pin "4") (pinfunction "P_4") (pintype "passive"))
      (node (ref "Q7") (pin "E") (pinfunction "E_E") (pintype "passive"))
      (node (ref "Q8") (pin "E") (pinfunction "E_E") (pintype "passive"))
      (node (ref "R1") (pin "2") (pinfunction "2_2") (pintype "passive"))
      (node (ref "R2") (pin "2") (pinfunction "2_2") (pintype "passive"))
      (node (ref "R30") (pin "1") (pinfunction "1_1") (pintype "passive"))
      (node (ref "R30_2") (pin "1") (pinfunction "1_1") (pintype "passive"))
      (node (ref "R33") (pin "1") (pinfunction "1_1") (pintype "passive"))
      (node (ref "R35") (pin "1") (pinfunction "1_1") (pintype "passive"))
      (node (ref "R37") (pin "1") (pinfunction "1_1") (pintype "passive"))
      (node (ref "R4") (pin "1") (pinfunction "1_1") (pintype "passive"))
      (node (ref "R40") (pin "1") (pinfunction "1_1") (pintype "passive"))
      (node (ref "R44") (pin "1") (pinfunction "1_1") (pintype "passive"))
      (node (ref "R46") (pin "1") (pinfunction "1_1") (pintype "passive"))
      (node (ref "R48") (pin "1") (pinfunction "1_1") (pintype "passive"))
      (node (ref "R51") (pin "1") (pinfunction "1_1") (pintype "passive"))
      (node (ref "R6") (pin "1") (pinfunction "1_1") (pintype "passive"))
      (node (ref "RIGHT") (pin "3") (pinfunction "P_3") (pintype "passive"))
      (node (ref "RIGHT") (pin "4") (pinfunction "P_4") (pintype "passive"))
      (node (ref "U1") (pin "18") (pinfunction "GND1_18") (pintype "power_in"))
      (node (ref "U1") (pin "28") (pinfunction "GND_28") (pintype "power_in"))
      (node (ref "U1") (pin "39") (pinfunction "GND2_39") (pintype "power_in"))
      (node (ref "U1") (pin "6") (pinfunction "GND_6") (pintype "power_in"))
      (node (ref "U10") (pin "4") (pinfunction "V-_4") (pintype "power_in"))
      (node (ref "U3") (pin "7") (pinfunction "VSS_7") (pintype "power_in"))
      (node (ref "U8B") (pin "7") (pinfunction "GND_7") (pintype "power_in"))
    )
    (net (code "5") (name "Net-(BATA-S)") (class "Default")
      (node (ref "BAT") (pin "1") (pinfunction "S_1") (pintype "passive"))
      (node (ref "P_SWITCH") (pin "2") (pinfunction "2_2") (pintype "bidirectional"))
    )
    (net (code "6") (name "Net-(CHAN_A-Pad1)") (class "Default")
      (node (ref "CHAN_A") (pin "1") (pinfunction "1_1") (pintype "bidirectional"))
      (node (ref "TR1") (pin "3") (pinfunction "3_3") (pintype "passive"))
    )
    (net (code "7") (name "Net-(CHAN_A-Pad3)") (class "Default")
      (node (ref "CHAN_A") (pin "3") (pinfunction "3_3") (pintype "bidirectional"))
      (node (ref "TR1") (pin "1") (pinfunction "1_1") (pintype "passive"))
    )
    (net (code "8") (name "Net-(CHAN_B-Pad1)") (class "Default")
      (node (ref "CHAN_B") (pin "1") (pinfunction "1_1") (pintype "bidirectional"))
      (node (ref "TR2") (pin "3") (pinfunction "3_3") (pintype "passive"))
    )
    (net (code "9") (name "Net-(CHAN_B-Pad3)") (class "Default")
      (node (ref "CHAN_B") (pin "3") (pinfunction "3_3") (pintype "bidirectional"))
      (node (ref "TR2") (pin "1") (pinfunction "1_1") (pintype "passive"))
    )
    (net (code "10") (name "Net-(DC_IN-CENTER_PIN)") (class "Default")
      (node (ref "DC_IN") (pin "1") (pinfunction "CENTER_PIN_1") (pintype "bidirectional"))
      (node (ref "P_SWITCH") (pin "1") (pinfunction "1_1") (pintype "bidirectional"))
    )
    (net (code "11") (name "Net-(F1-Pad1)") (class "Default")
      (node (ref "F1") (pin "1") (pinfunction "1_1") (pintype "passive"))
      (node (ref "P_SWITCH") (pin "3") (pinfunction "3_3") (pintype "bidirectional"))
    )
    (net (code "12") (name "Net-(IC1-CB)") (class "Default")
      (node (ref "C9") (pin "1") (pinfunction "1_1") (pintype "passive"))
      (node (ref "IC1") (pin "1") (pinfunction "CB_1") (pintype "input"))
    )
    (net (code "13") (name "Net-(IC1-OUT)") (class "Default")
      (node (ref "C9") (pin "2") (pinfunction "2_2") (pintype "passive"))
      (node (ref "D2") (pin "C") (pinfunction "C_C") (pintype "passive"))
      (node (ref "IC1") (pin "8") (pinfunction "OUT_8") (pintype "passive"))
      (node (ref "L1") (pin "1") (pinfunction "1_1") (pintype "passive"))
    )
    (net (code "14") (name "Net-(LCD1-A)") (class "Default")
      (node (ref "LCD1") (pin "15") (pinfunction "A_15") (pintype "input"))
      (node (ref "R12") (pin "1") (pinfunction "1_1") (pintype "passive"))
    )
    (net (code "15") (name "Net-(LCD1-K)") (class "Default")
      (node (ref "LCD1") (pin "16") (pinfunction "K_16") (pintype "input"))
      (node (ref "Q8") (pin "C") (pinfunction "C_C") (pintype "passive"))
    )
    (net (code "16") (name "Net-(LCD1-VO)") (class "Default")
      (node (ref "CONTR.") (pin "S") (pinfunction "S_S") (pintype "passive"))
      (node (ref "LCD1") (pin "3") (pinfunction "VO_3") (pintype "input"))
    )
    (net (code "17") (name "Net-(LED_CH_A-PadA)") (class "Default")
      (node (ref "LED_CH_A") (pin "A") (pinfunction "A_A") (pintype "passive"))
      (node (ref "R54") (pin "1") (pinfunction "1_1") (pintype "passive"))
    )
    (net (code "18") (name "Net-(LED_CH_B-PadA)") (class "Default")
      (node (ref "LED_CH_B") (pin "A") (pinfunction "A_A") (pintype "passive"))
      (node (ref "R53") (pin "1") (pinfunction "1_1") (pintype "passive"))
    )
    (net (code "19") (name "Net-(LED_POWER-PadA)") (class "Default")
      (node (ref "LED_POWER") (pin "A") (pinfunction "A_A") (pintype "passive"))
      (node (ref "R60") (pin "1") (pinfunction "1_1") (pintype "passive"))
    )
    (net (code "20") (name "Net-(MULTI-E)") (class "Default")
      (node (ref "MULTI") (pin "3") (pinfunction "E_3") (pintype "passive"))
      (node (ref "R7") (pin "1") (pinfunction "1_1") (pintype "passive"))
    )
    (net (code "21") (name "Net-(Q1-D-Pad2)") (class "Default")
      (node (ref "Q1") (pin "2") (pinfunction "D_2") (pintype "passive"))
      (node (ref "Q1") (pin "4") (pinfunction "D_4") (pintype "passive"))
      (node (ref "TR1") (pin "4") (pinfunction "4_4") (pintype "passive"))
    )
    (net (code "22") (name "Net-(Q1-G)") (class "Default")
      (node (ref "Q1") (pin "1") (pinfunction "G_1") (pintype "passive"))
      (node (ref "R38") (pin "2") (pinfunction "2_2") (pintype "passive"))
    )
    (net (code "23") (name "Net-(Q2-D-Pad2)") (class "Default")
      (node (ref "Q2") (pin "2") (pinfunction "D_2") (pintype "passive"))
      (node (ref "Q2") (pin "4") (pinfunction "D_4") (pintype "passive"))
      (node (ref "TR1") (pin "6") (pinfunction "6_6") (pintype "passive"))
    )
    (net (code "24") (name "Net-(Q2-G)") (class "Default")
      (node (ref "Q2") (pin "1") (pinfunction "G_1") (pintype "passive"))
      (node (ref "R41") (pin "2") (pinfunction "2_2") (pintype "passive"))
    )
    (net (code "25") (name "Net-(Q3-D-Pad2)") (class "Default")
      (node (ref "Q3") (pin "2") (pinfunction "D_2") (pintype "passive"))
      (node (ref "Q3") (pin "4") (pinfunction "D_4") (pintype "passive"))
      (node (ref "TR1") (pin "5") (pinfunction "5_5") (pintype "passive"))
    )
    (net (code "26") (name "Net-(Q3-G)") (class "Default")
      (node (ref "C39") (pin "1") (pinfunction "1_1") (pintype "passive"))
      (node (ref "Q3") (pin "1") (pinfunction "G_1") (pintype "passive"))
      (node (ref "R39") (pin "2") (pinfunction "2_2") (pintype "passive"))
    )
    (net (code "27") (name "Net-(Q4-D-Pad2)") (class "Default")
      (node (ref "Q4") (pin "2") (pinfunction "D_2") (pintype "passive"))
      (node (ref "Q4") (pin "4") (pinfunction "D_4") (pintype "passive"))
      (node (ref "TR2") (pin "4") (pinfunction "4_4") (pintype "passive"))
    )
    (net (code "28") (name "Net-(Q4-G)") (class "Default")
      (node (ref "Q4") (pin "1") (pinfunction "G_1") (pintype "passive"))
      (node (ref "R49") (pin "2") (pinfunction "2_2") (pintype "passive"))
    )
    (net (code "29") (name "Net-(Q5-D-Pad2)") (class "Default")
      (node (ref "Q5") (pin "2") (pinfunction "D_2") (pintype "passive"))
      (node (ref "Q5") (pin "4") (pinfunction "D_4") (pintype "passive"))
      (node (ref "TR2") (pin "6") (pinfunction "6_6") (pintype "passive"))
    )
    (net (code "30") (name "Net-(Q5-G)") (class "Default")
      (node (ref "Q5") (pin "1") (pinfunction "G_1") (pintype "passive"))
      (node (ref "R52") (pin "2") (pinfunction "2_2") (pintype "passive"))
    )
    (net (code "31") (name "Net-(Q6-D-Pad2)") (class "Default")
      (node (ref "Q6") (pin "2") (pinfunction "D_2") (pintype "passive"))
      (node (ref "Q6") (pin "4") (pinfunction "D_4") (pintype "passive"))
      (node (ref "TR2") (pin "5") (pinfunction "5_5") (pintype "passive"))
    )
    (net (code "32") (name "Net-(Q6-G)") (class "Default")
      (node (ref "C40") (pin "1") (pinfunction "1_1") (pintype "passive"))
      (node (ref "Q6") (pin "1") (pinfunction "G_1") (pintype "passive"))
      (node (ref "R50") (pin "2") (pinfunction "2_2") (pintype "passive"))
    )
    (net (code "33") (name "Net-(Q7-PadB)") (class "Default")
      (node (ref "Q7") (pin "B") (pinfunction "B_B") (pintype "passive"))
      (node (ref "R56") (pin "1") (pinfunction "1_1") (pintype "passive"))
    )
    (net (code "34") (name "Net-(Q7-PadC)") (class "Default")
      (node (ref "Q7") (pin "C") (pinfunction "C_C") (pintype "passive"))
      (node (ref "Q8") (pin "B") (pinfunction "B_B") (pintype "passive"))
      (node (ref "R57") (pin "2") (pinfunction "2_2") (pintype "passive"))
    )
    (net (code "35") (name "Net-(U1-(ADC2)PA2)") (class "Default")
      (node (ref "R4") (pin "2") (pinfunction "2_2") (pintype "passive"))
      (node (ref "U1") (pin "35") (pinfunction "(ADC2)PA2_35") (pintype "bidirectional"))
    )
    (net (code "36") (name "Net-(U1-(ADC3)PA3)") (class "Default")
      (node (ref "R5") (pin "1") (pinfunction "1_1") (pintype "passive"))
      (node (ref "R6") (pin "2") (pinfunction "2_2") (pintype "passive"))
      (node (ref "U1") (pin "34") (pinfunction "(ADC3)PA3_34") (pintype "bidirectional"))
    )
    (net (code "37") (name "Net-(U1-(ADC6)PA6)") (class "Default")
      (node (ref "R2") (pin "1") (pinfunction "1_1") (pintype "passive"))
      (node (ref "U1") (pin "31") (pinfunction "(ADC6)PA6_31") (pintype "bidirectional"))
    )
    (net (code "38") (name "Net-(U1-(ADC7)PA7)") (class "Default")
      (node (ref "R1") (pin "1") (pinfunction "1_1") (pintype "passive"))
      (node (ref "U1") (pin "30") (pinfunction "(ADC7)PA7_30") (pintype "bidirectional"))
    )
    (net (code "39") (name "Net-(U1-(RXD)PD0)") (class "Default")
      (node (ref "U1") (pin "9") (pinfunction "(RXD)PD0_9") (pintype "bidirectional"))
      (node (ref "UART") (pin "2") (pinfunction "2_2") (pintype "passive"))
    )
    (net (code "40") (name "Net-(U1-(TXD)PD1)") (class "Default")
      (node (ref "U1") (pin "10") (pinfunction "(TXD)PD1_10") (pintype "bidirectional"))
      (node (ref "UART") (pin "1") (pinfunction "1_1") (pintype "passive"))
    )
    (net (code "41") (name "Net-(U1-XTAL1)") (class "Default")
      (node (ref "C16") (pin "1") (pinfunction "1_1") (pintype "passive"))
      (node (ref "U1") (pin "8") (pinfunction "XTAL1_8") (pintype "bidirectional"))
      (node (ref "Y1") (pin "2") (pinfunction "2_2") (pintype "passive"))
    )
    (net (code "42") (name "Net-(U1-XTAL2)") (class "Default")
      (node (ref "C15") (pin "1") (pinfunction "1_1") (pintype "passive"))
      (node (ref "U1") (pin "7") (pinfunction "XTAL2_7") (pintype "bidirectional"))
      (node (ref "Y1") (pin "1") (pinfunction "1_1") (pintype "passive"))
    )
    (net (code "43") (name "Net-(U3A-A)") (class "Default")
      (node (ref "C7") (pin "1") (pinfunction "1_1") (pintype "passive"))
      (node (ref "MENU") (pin "1") (pinfunction "S_1") (pintype "passive"))
      (node (ref "MENU") (pin "2") (pinfunction "S_2") (pintype "passive"))
      (node (ref "R11") (pin "2") (pinfunction "2_2") (pintype "passive"))
      (node (ref "U3") (pin "1") (pinfunction "A_1") (pintype "tri_state"))
    )
    (net (code "44") (name "Net-(U3B-A)") (class "Default")
      (node (ref "C5") (pin "1") (pinfunction "1_1") (pintype "passive"))
      (node (ref "R10") (pin "2") (pinfunction "2_2") (pintype "passive"))
      (node (ref "RIGHT") (pin "1") (pinfunction "S_1") (pintype "passive"))
      (node (ref "RIGHT") (pin "2") (pinfunction "S_2") (pintype "passive"))
      (node (ref "U3") (pin "4") (pinfunction "A_4") (pintype "tri_state"))
    )
    (net (code "45") (name "Net-(U3C-A)") (class "Default")
      (node (ref "C4") (pin "1") (pinfunction "1_1") (pintype "passive"))
      (node (ref "OK") (pin "1") (pinfunction "S_1") (pintype "passive"))
      (node (ref "OK") (pin "2") (pinfunction "S_2") (pintype "passive"))
      (node (ref "R9") (pin "2") (pinfunction "2_2") (pintype "passive"))
      (node (ref "U3") (pin "8") (pinfunction "A_8") (pintype "tri_state"))
    )
    (net (code "46") (name "Net-(U3D-A)") (class "Default")
      (node (ref "C3") (pin "1") (pinfunction "1_1") (pintype "passive"))
      (node (ref "LEFT") (pin "1") (pinfunction "S_1") (pintype "passive"))
      (node (ref "LEFT") (pin "2") (pinfunction "S_2") (pintype "passive"))
      (node (ref "R8") (pin "2") (pinfunction "2_2") (pintype "passive"))
      (node (ref "U3") (pin "11") (pinfunction "A_11") (pintype "tri_state"))
    )
    (net (code "47") (name "Net-(U8B-VOUT_A)") (class "Default")
      (node (ref "R42") (pin "1") (pinfunction "1_1") (pintype "passive"))
      (node (ref "U8B") (pin "8") (pinfunction "VOUT_A_8") (pintype "output"))
    )
    (net (code "48") (name "Net-(U8B-VOUT_B)") (class "Default")
      (node (ref "R31") (pin "1") (pinfunction "1_1") (pintype "passive"))
      (node (ref "U8B") (pin "5") (pinfunction "VOUT_B_5") (pintype "output"))
    )
    (net (code "49") (name "Net-(U10A-+IN)") (class "Default")
      (node (ref "R31") (pin "2") (pinfunction "2_2") (pintype "passive"))
      (node (ref "R32") (pin "1") (pinfunction "1_1") (pintype "passive"))
      (node (ref "R33") (pin "2") (pinfunction "2_2") (pintype "passive"))
      (node (ref "U10") (pin "3") (pinfunction "+IN_3") (pintype "input"))
    )
    (net (code "50") (name "Net-(U10A--IN)") (class "Default")
      (node (ref "R34") (pin "1") (pinfunction "1_1") (pintype "passive"))
      (node (ref "R35") (pin "2") (pinfunction "2_2") (pintype "passive"))
      (node (ref "R36") (pin "1") (pinfunction "1_1") (pintype "passive"))
      (node (ref "U10") (pin "2") (pinfunction "-IN_2") (pintype "input"))
    )
    (net (code "51") (name "Net-(U10A-OUT)") (class "Default")
      (node (ref "R36") (pin "2") (pinfunction "2_2") (pintype "passive"))
      (node (ref "R39") (pin "1") (pinfunction "1_1") (pintype "passive"))
      (node (ref "U10") (pin "1") (pinfunction "OUT_1") (pintype "output"))
    )
    (net (code "52") (name "Net-(U10B-+IN)") (class "Default")
      (node (ref "R42") (pin "2") (pinfunction "2_2") (pintype "passive"))
      (node (ref "R43") (pin "1") (pinfunction "1_1") (pintype "passive"))
      (node (ref "R44") (pin "2") (pinfunction "2_2") (pintype "passive"))
      (node (ref "U10") (pin "5") (pinfunction "+IN_5") (pintype "input"))
    )
    (net (code "53") (name "Net-(U10B--IN)") (class "Default")
      (node (ref "R45") (pin "1") (pinfunction "1_1") (pintype "passive"))
      (node (ref "R46") (pin "2") (pinfunction "2_2") (pintype "passive"))
      (node (ref "R47") (pin "1") (pinfunction "1_1") (pintype "passive"))
      (node (ref "U10") (pin "6") (pinfunction "-IN_6") (pintype "input"))
    )
    (net (code "54") (name "Net-(U10B-OUT)") (class "Default")
      (node (ref "R47") (pin "2") (pinfunction "2_2") (pintype "passive"))
      (node (ref "R50") (pin "1") (pinfunction "1_1") (pintype "passive"))
      (node (ref "U10") (pin "7") (pinfunction "OUT_7") (pintype "output"))
    )
    (net (code "55") (name "PA0") (class "Default")
      (node (ref "Q1") (pin "3") (pinfunction "S_3") (pintype "passive"))
      (node (ref "Q2") (pin "3") (pinfunction "S_3") (pintype "passive"))
      (node (ref "Q4") (pin "3") (pinfunction "S_3") (pintype "passive"))
      (node (ref "Q5") (pin "3") (pinfunction "S_3") (pintype "passive"))
      (node (ref "R30") (pin "2") (pinfunction "2_2") (pintype "passive"))
      (node (ref "R30_2") (pin "2") (pinfunction "2_2") (pintype "passive"))
      (node (ref "U1") (pin "37") (pinfunction "(ADC0)PA0_37") (pintype "bidirectional"))
    )
    (net (code "56") (name "PA1") (class "Default")
      (node (ref "MULTI") (pin "2") (pinfunction "S_2") (pintype "passive"))
      (node (ref "U1") (pin "36") (pinfunction "(ADC1)PA1_36") (pintype "bidirectional"))
    )
    (net (code "57") (name "PA4") (class "Default")
      (node (ref "LEVEL_A") (pin "2") (pinfunction "S_2") (pintype "passive"))
      (node (ref "U1") (pin "33") (pinfunction "(ADC4)PA4_33") (pintype "bidirectional"))
    )
    (net (code "58") (name "PA5") (class "Default")
      (node (ref "LEVEL_B") (pin "2") (pinfunction "S_2") (pintype "passive"))
      (node (ref "U1") (pin "32") (pinfunction "(ADC5)PA5_32") (pintype "bidirectional"))
    )
    (net (code "59") (name "PB0") (class "Default")
      (node (ref "R48") (pin "2") (pinfunction "2_2") (pintype "passive"))
      (node (ref "R49") (pin "1") (pinfunction "1_1") (pintype "passive"))
      (node (ref "U1") (pin "40") (pinfunction "(T0/XCK)PB0_40") (pintype "bidirectional"))
    )
    (net (code "60") (name "PB1") (class "Default")
      (node (ref "R51") (pin "2") (pinfunction "2_2") (pintype "passive"))
      (node (ref "R52") (pin "1") (pinfunction "1_1") (pintype "passive"))
      (node (ref "U1") (pin "41") (pinfunction "(T1)PB1_41") (pintype "bidirectional"))
    )
    (net (code "61") (name "PB2") (class "Default")
      (node (ref "R37") (pin "2") (pinfunction "2_2") (pintype "passive"))
      (node (ref "R38") (pin "1") (pinfunction "1_1") (pintype "passive"))
      (node (ref "U1") (pin "42") (pinfunction "(AIN0/INT2)PB2_42") (pintype "bidirectional"))
    )
    (net (code "62") (name "PB3") (class "Default")
      (node (ref "R40") (pin "2") (pinfunction "2_2") (pintype "passive"))
      (node (ref "R41") (pin "1") (pinfunction "1_1") (pintype "passive"))
      (node (ref "U1") (pin "43") (pinfunction "(AIN1/OC0)PB3_43") (pintype "bidirectional"))
    )
    (net (code "63") (name "PB5") (class "Default")
      (node (ref "ISP1") (pin "4") (pinfunction "MOSI_4") (pintype "output"))
      (node (ref "U1") (pin "1") (pinfunction "(MOSI)PB5_1") (pintype "bidirectional"))
      (node (ref "U8B") (pin "3") (pinfunction "D_IN_3") (pintype "input"))
    )
    (net (code "64") (name "PB6") (class "Default")
      (node (ref "ISP1") (pin "1") (pinfunction "MISO_1") (pintype "input"))
      (node (ref "U1") (pin "2") (pinfunction "(MISO)PB6_2") (pintype "bidirectional"))
    )
    (net (code "65") (name "PB7") (class "Default")
      (node (ref "ISP1") (pin "3") (pinfunction "SCK_3") (pintype "output"))
      (node (ref "U1") (pin "3") (pinfunction "(SCK)PB7_3") (pintype "bidirectional"))
      (node (ref "U8B") (pin "2") (pinfunction "SCK_2") (pintype "input"))
    )
    (net (code "66") (name "PC0") (class "Default")
      (node (ref "U1") (pin "19") (pinfunction "PC0(SCL)_19") (pintype "bidirectional"))
      (node (ref "U3") (pin "12") (pinfunction "C_12") (pintype "input"))
      (node (ref "U3") (pin "13") (pinfunction "C_13") (pintype "input"))
      (node (ref "U3") (pin "5") (pinfunction "C_5") (pintype "input"))
      (node (ref "U3") (pin "6") (pinfunction "C_6") (pintype "input"))
    )
    (net (code "67") (name "PC1") (class "Default")
      (node (ref "LCD1") (pin "5") (pinfunction "RW_5") (pintype "input"))
      (node (ref "U1") (pin "20") (pinfunction "PC1(SDA)_20") (pintype "bidirectional"))
    )
    (net (code "68") (name "PC2") (class "Default")
      (node (ref "LCD1") (pin "6") (pinfunction "E_6") (pintype "input"))
      (node (ref "U1") (pin "21") (pinfunction "(TCK)PC2_21") (pintype "bidirectional"))
    )
    (net (code "69") (name "PC3") (class "Default")
      (node (ref "LCD1") (pin "4") (pinfunction "RS_4") (pintype "input"))
      (node (ref "U1") (pin "22") (pinfunction "(TMS)PC3_22") (pintype "bidirectional"))
    )
    (net (code "70") (name "PC4") (class "Default")
      (node (ref "LCD1") (pin "11") (pinfunction "DB4_11") (pintype "bidirectional"))
      (node (ref "U1") (pin "23") (pinfunction "(TDO)PC4_23") (pintype "bidirectional"))
      (node (ref "U3") (pin "10") (pinfunction "B_10") (pintype "tri_state"))
    )
    (net (code "71") (name "PC5") (class "Default")
      (node (ref "LCD1") (pin "12") (pinfunction "DB5_12") (pintype "bidirectional"))
      (node (ref "U1") (pin "24") (pinfunction "(TDI)PC5_24") (pintype "bidirectional"))
      (node (ref "U3") (pin "9") (pinfunction "B_9") (pintype "tri_state"))
    )
    (net (code "72") (name "PC6") (class "Default")
      (node (ref "LCD1") (pin "13") (pinfunction "DB6_13") (pintype "bidirectional"))
      (node (ref "U1") (pin "25") (pinfunction "(TOSC1)PC6_25") (pintype "bidirectional"))
      (node (ref "U3") (pin "3") (pinfunction "B_3") (pintype "tri_state"))
    )
    (net (code "73") (name "PC7") (class "Default")
      (node (ref "LCD1") (pin "14") (pinfunction "DB7_14") (pintype "bidirectional"))
      (node (ref "U1") (pin "26") (pinfunction "(TOSC2)PC7_26") (pintype "bidirectional"))
      (node (ref "U3") (pin "2") (pinfunction "B_2") (pintype "tri_state"))
    )
    (net (code "74") (name "PD5") (class "Default")
      (node (ref "LED_CH_B") (pin "K") (pinfunction "C_K") (pintype "passive"))
      (node (ref "U1") (pin "14") (pinfunction "(OC1A)PD5_14") (pintype "bidirectional"))
    )
    (net (code "75") (name "PD6") (class "Default")
      (node (ref "LED_CH_A") (pin "K") (pinfunction "C_K") (pintype "passive"))
      (node (ref "U1") (pin "15") (pinfunction "(ICP)PD6_15") (pintype "bidirectional"))
    )
    (net (code "76") (name "PD7") (class "Default")
      (node (ref "R56") (pin "2") (pinfunction "2_2") (pintype "passive"))
      (node (ref "U1") (pin "16") (pinfunction "(OC2)PD7_16") (pintype "bidirectional"))
    )
    (net (code "77") (name "RESET") (class "Default")
      (node (ref "C8") (pin "1") (pinfunction "1_1") (pintype "passive"))
      (node (ref "ISP1") (pin "5") (pinfunction "RST_5") (pintype "output"))
      (node (ref "R3") (pin "1") (pinfunction "1_1") (pintype "passive"))
      (node (ref "U1") (pin "4") (pinfunction "RESET_4") (pintype "input"))
    )
    (net (code "78") (name "unconnected-(CHAN_A-Pad2)") (class "Default")
      (node (ref "CHAN_A") (pin "2") (pinfunction "2_2") (pintype "bidirectional"))
    )
    (net (code "79") (name "unconnected-(CHAN_B-Pad2)") (class "Default")
      (node (ref "CHAN_B") (pin "2") (pinfunction "2_2") (pintype "bidirectional"))
    )
    (net (code "80") (name "unconnected-(DC_IN-SLEEVE_SHUNT-Pad2)") (class "Default")
      (node (ref "DC_IN") (pin "2") (pinfunction "SLEEVE_SHUNT_2") (pintype "bidirectional"))
    )
    (net (code "81") (name "unconnected-(IC1-~{ON{slash}OFF}-Pad5)") (class "Default")
      (node (ref "IC1") (pin "5") (pinfunction "~{ON/OFF}_5") (pintype "input"))
    )
    (net (code "82") (name "unconnected-(LCD1-DB0-Pad7)") (class "Default")
      (node (ref "LCD1") (pin "7") (pinfunction "DB0_7") (pintype "bidirectional"))
    )
    (net (code "83") (name "unconnected-(LCD1-DB1-Pad8)") (class "Default")
      (node (ref "LCD1") (pin "8") (pinfunction "DB1_8") (pintype "bidirectional"))
    )
    (net (code "84") (name "unconnected-(LCD1-DB2-Pad9)") (class "Default")
      (node (ref "LCD1") (pin "9") (pinfunction "DB2_9") (pintype "bidirectional"))
    )
    (net (code "85") (name "unconnected-(LCD1-DB3-Pad10)") (class "Default")
      (node (ref "LCD1") (pin "10") (pinfunction "DB3_10") (pintype "bidirectional"))
    )
    (net (code "86") (name "unconnected-(TR1-Pad2)") (class "Default")
      (node (ref "TR1") (pin "2") (pinfunction "2_2") (pintype "passive"))
    )
    (net (code "87") (name "unconnected-(TR2-Pad2)") (class "Default")
      (node (ref "TR2") (pin "2") (pinfunction "2_2") (pintype "passive"))
    )
    (net (code "88") (name "unconnected-(U1-(INT0)PD2-Pad11)") (class "Default")
      (node (ref "U1") (pin "11") (pinfunction "(INT0)PD2_11") (pintype "bidirectional"))
    )
    (net (code "89") (name "unconnected-(U1-(INT1)PD3-Pad12)") (class "Default")
      (node (ref "U1") (pin "12") (pinfunction "(INT1)PD3_12") (pintype "bidirectional"))
    )
    (net (code "90") (name "unconnected-(U1-(SS)PB4-Pad44)") (class "Default")
      (node (ref "U1") (pin "44") (pinfunction "(SS)PB4_44") (pintype "bidirectional"))
    )
    (net (code "91") (name "~{CS}") (class "Default")
      (node (ref "U1") (pin "13") (pinfunction "(OC1B)PD4_13") (pintype "bidirectional"))
      (node (ref "U8B") (pin "1") (pinfunction "CS/LD_1") (pintype "input"))
    )
  )
)
